# EEZ_XMOS_eval_r1B4.net
KiCad netlist of a schematic drawn in EAGLE
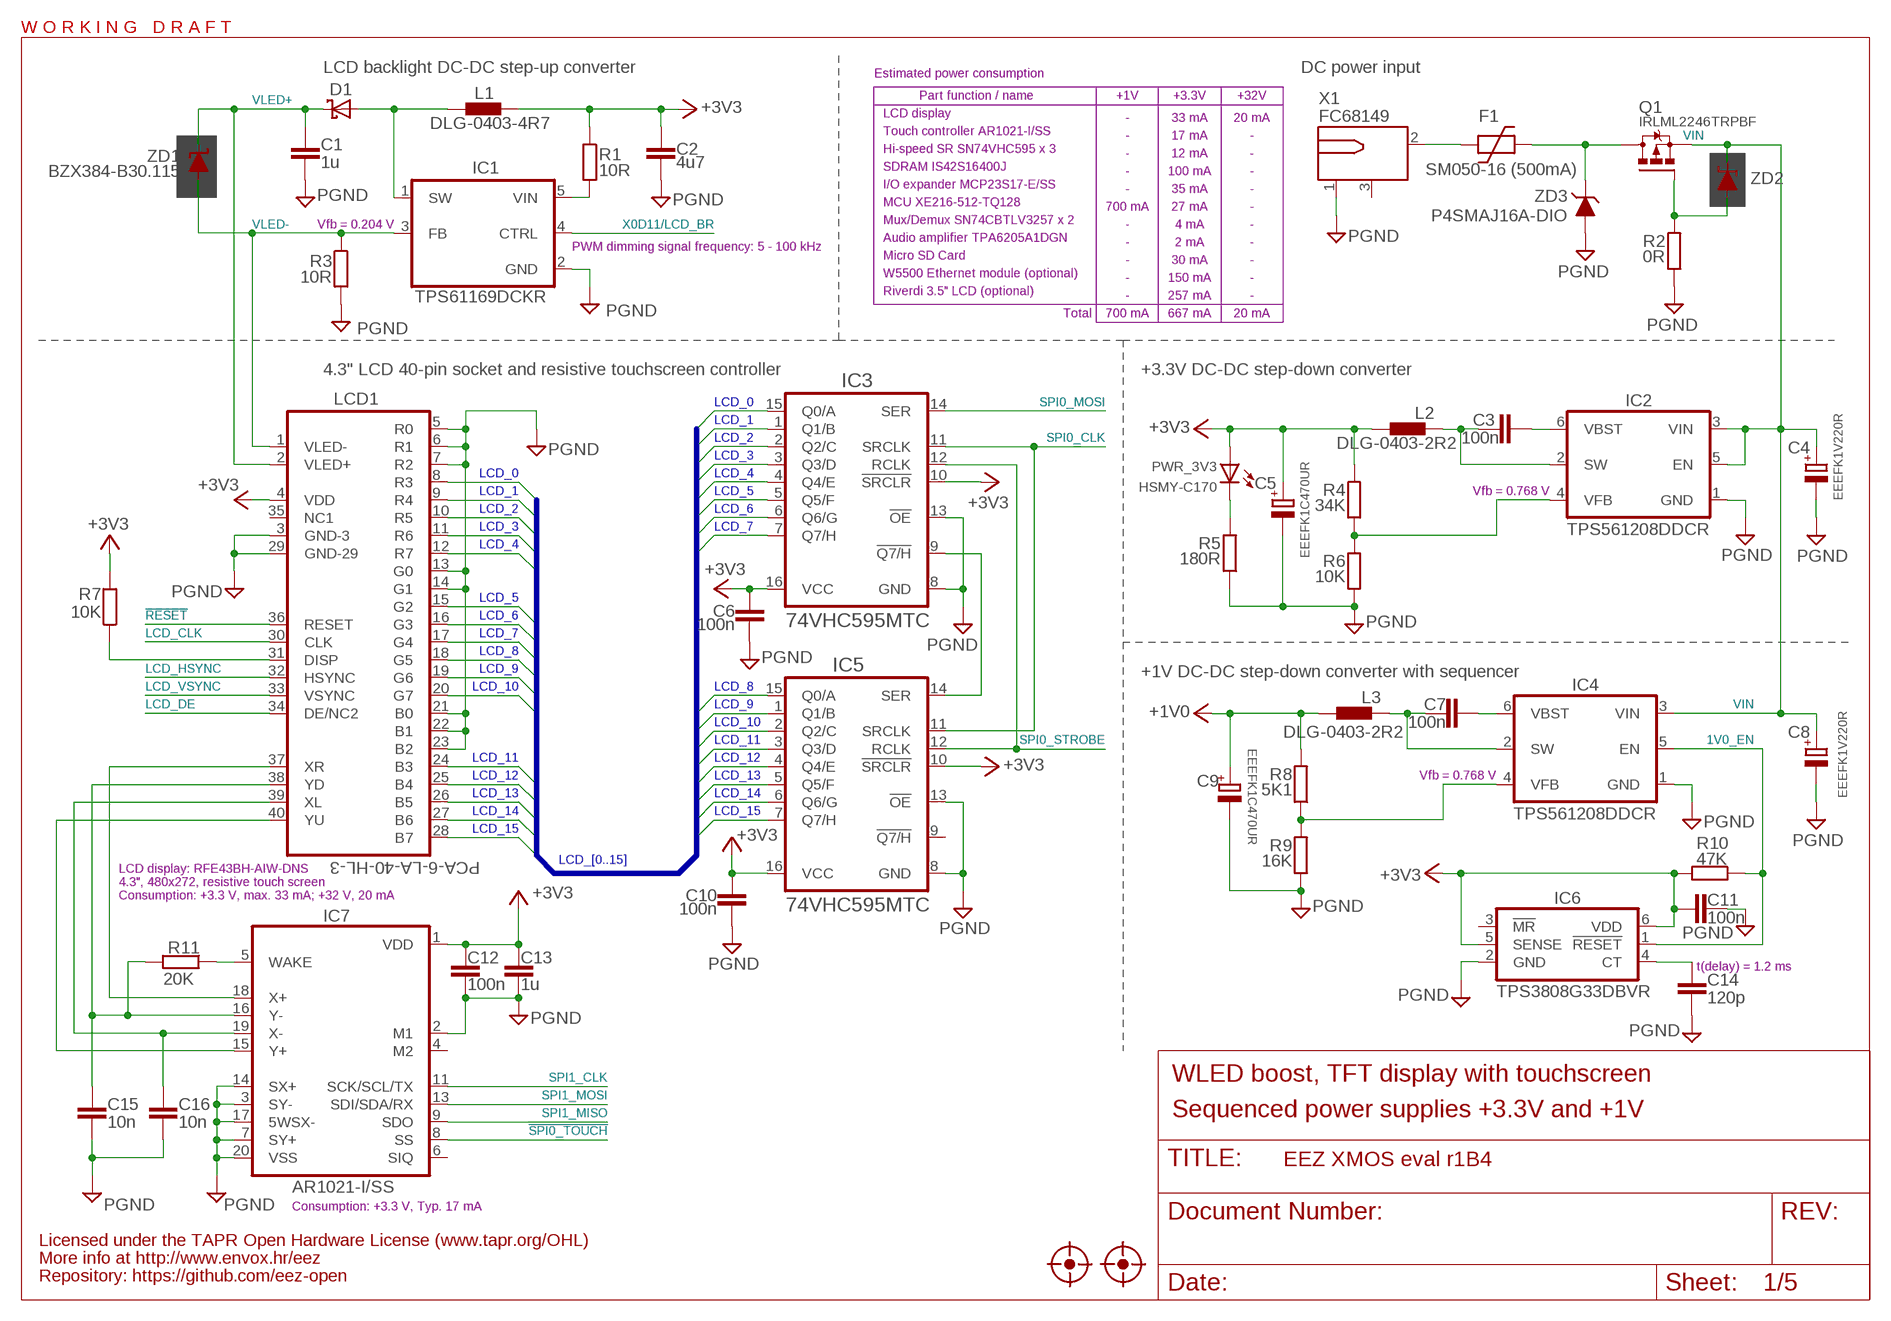
[diagram p0: schematic, sheet 1]
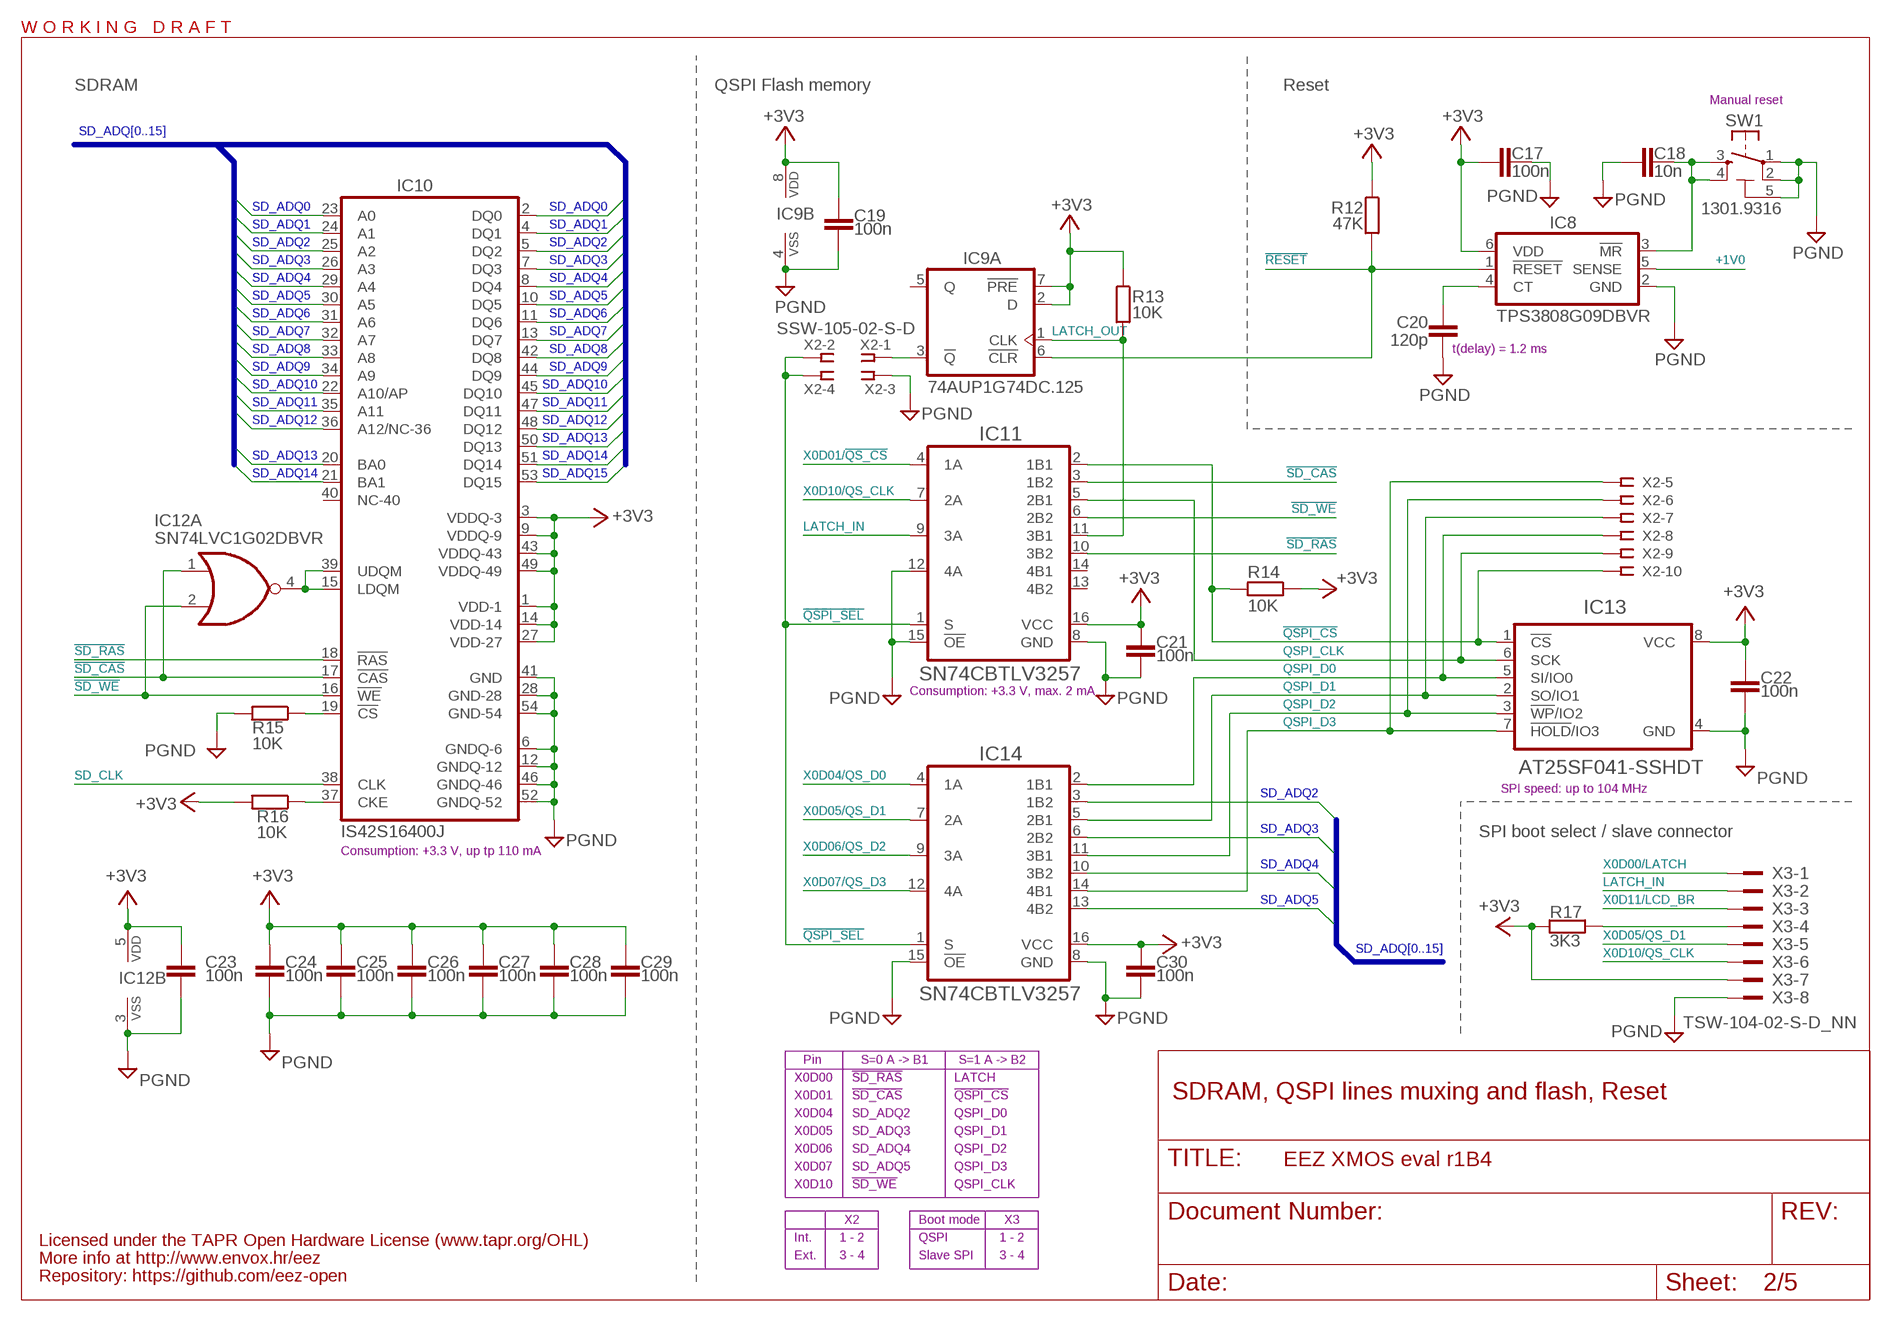
[diagram p1: schematic, sheet 2]
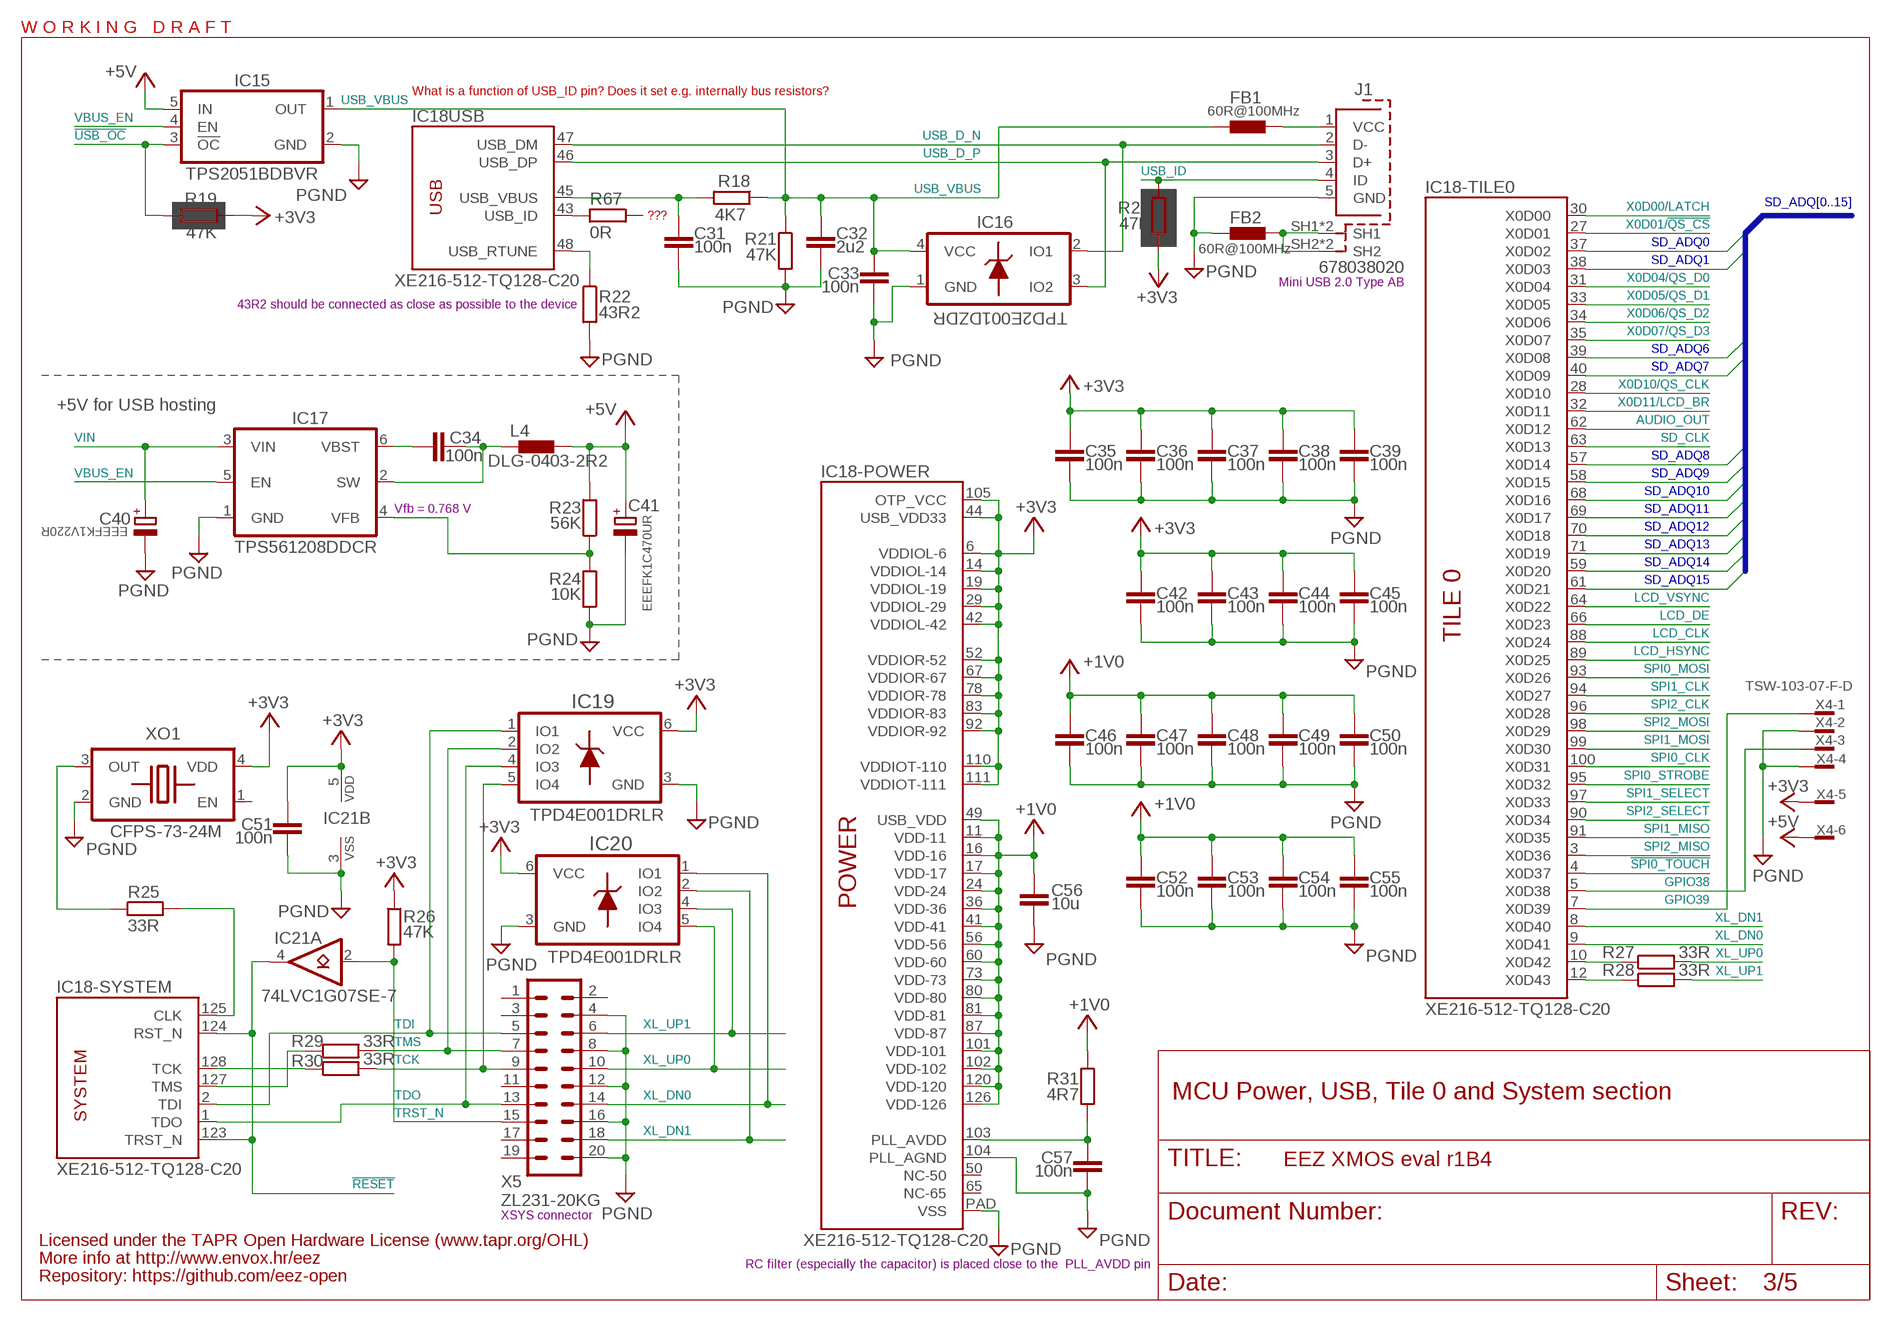
[diagram p2: schematic, sheet 3]
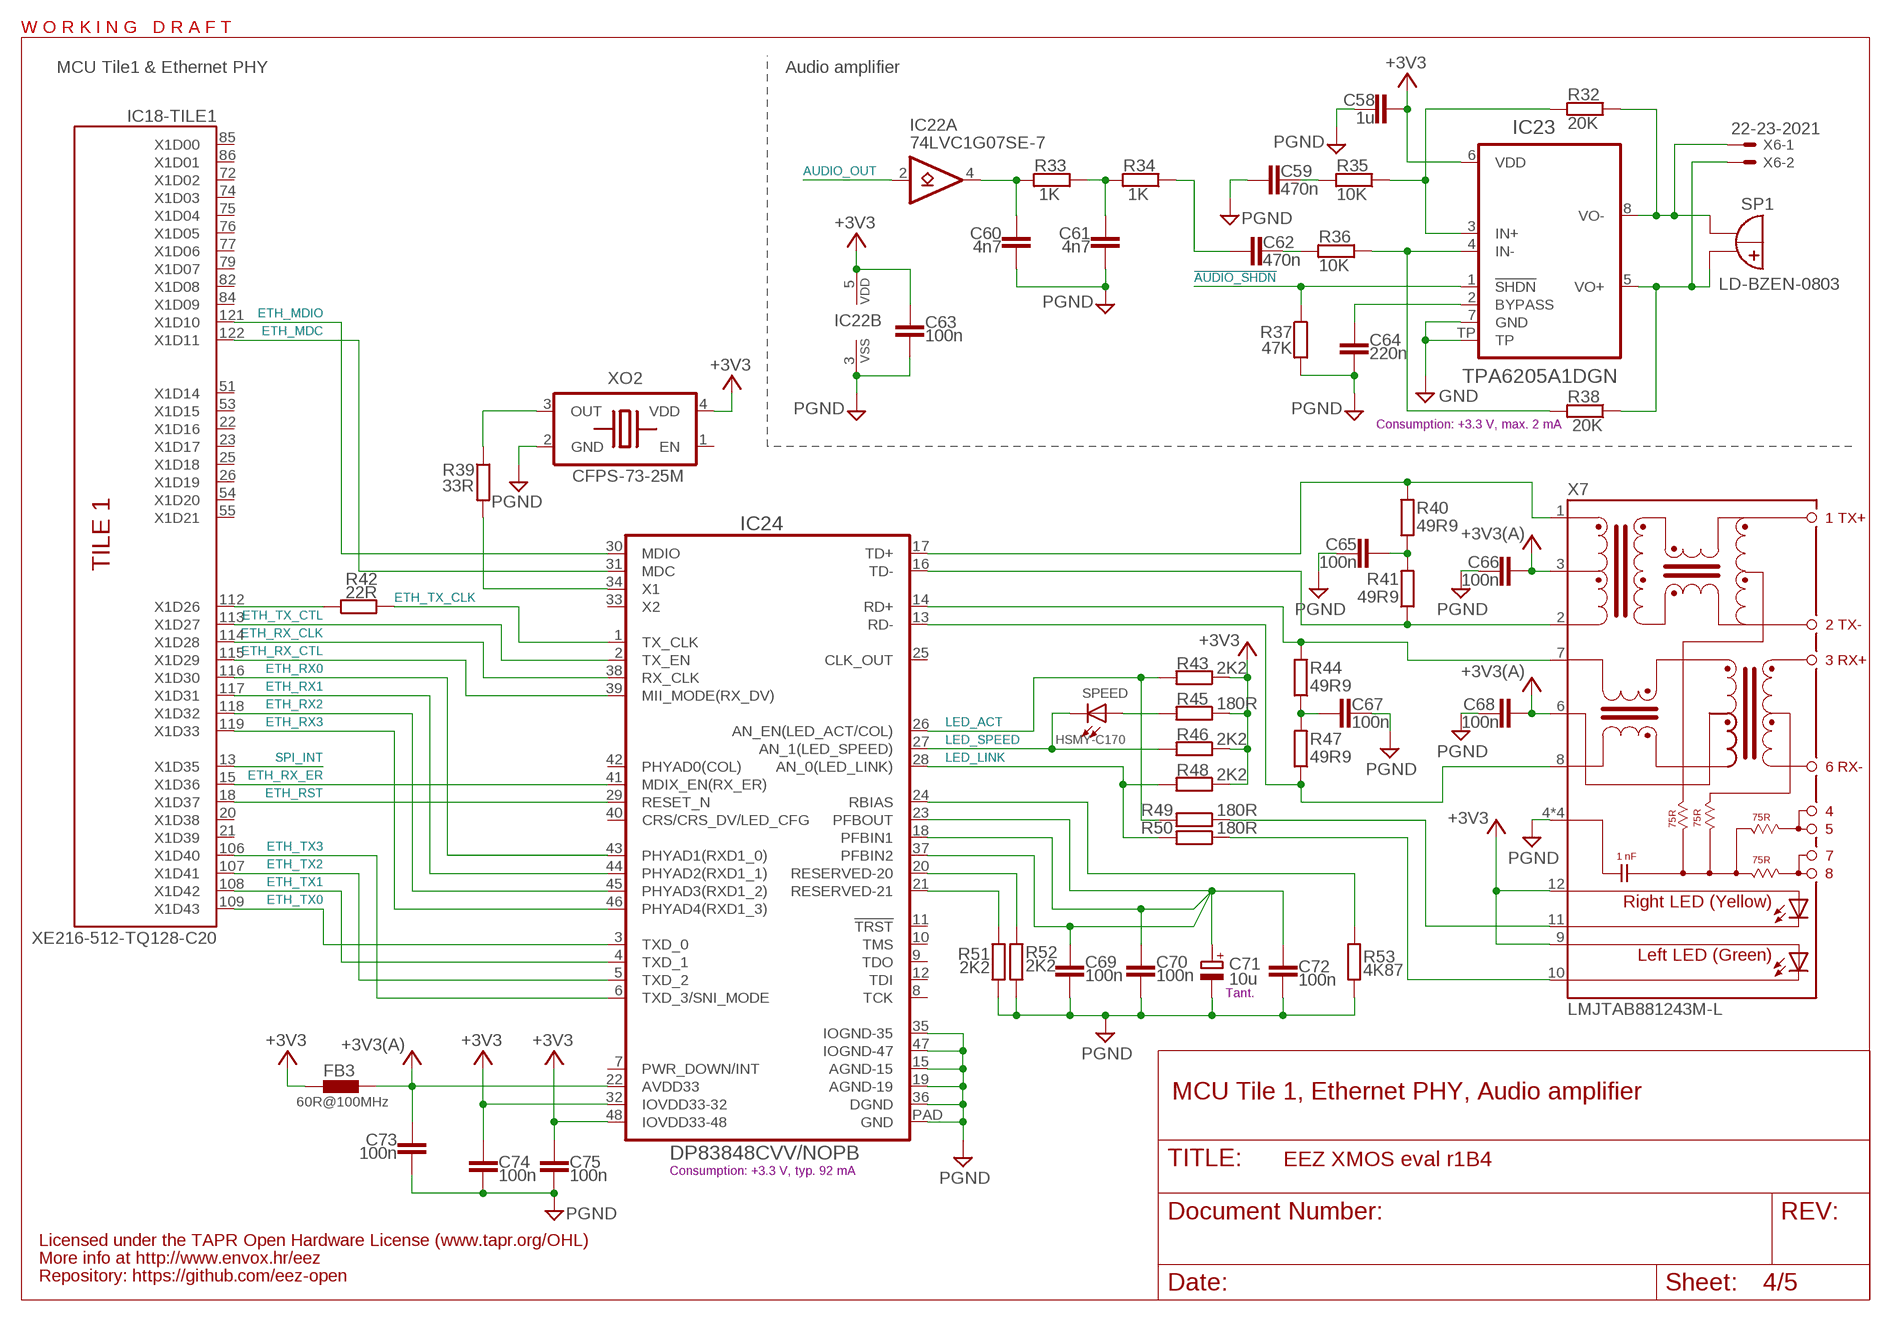
[diagram p3: schematic, sheet 4]
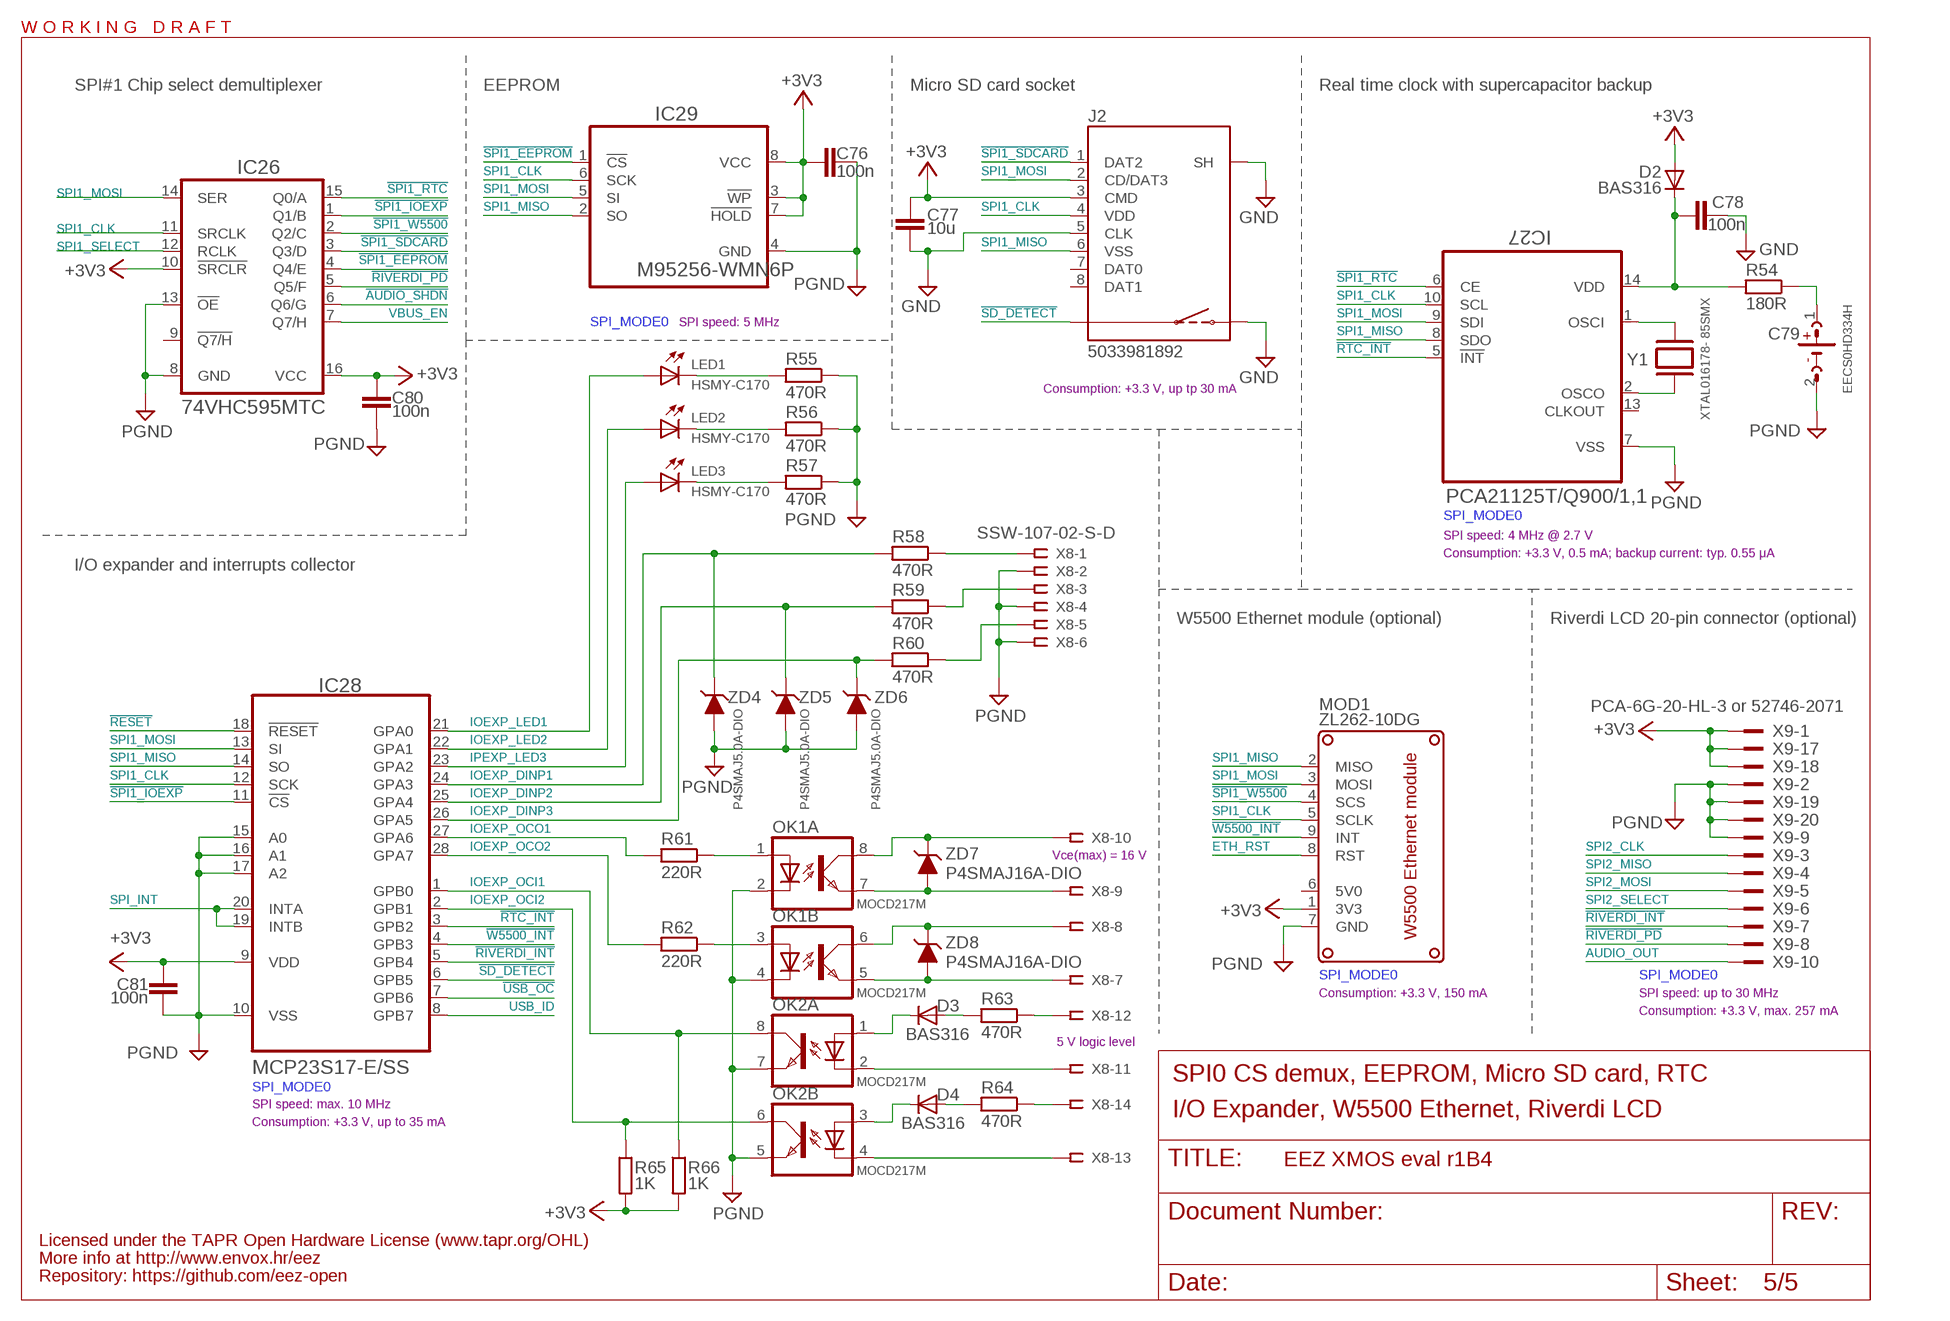
[diagram p4: schematic, sheet 5]

(export (version "E")
  (design (tool "Eeschema 10.0.6"))
  (components
    (comp (ref "C31")
      (value "100n")
      (footprint "eagle-import:C0603")
      (libsource (lib "eagle-import") (part "C-EUC0603"))
    )
    (comp (ref "C32")
      (value "2u2")
      (footprint "eagle-import:C0805")
      (libsource (lib "eagle-import") (part "C-EUC0805"))
    )
    (comp (ref "C33")
      (value "100n")
      (footprint "eagle-import:C0603")
      (libsource (lib "eagle-import") (part "C-EUC0603"))
    )
    (comp (ref "C34")
      (value "100n")
      (footprint "eagle-import:C0603")
      (libsource (lib "eagle-import") (part "C-EUC0603"))
    )
    (comp (ref "C35")
      (value "100n")
      (footprint "eagle-import:C0603")
      (libsource (lib "eagle-import") (part "C-EUC0603"))
    )
    (comp (ref "C36")
      (value "100n")
      (footprint "eagle-import:C0603")
      (libsource (lib "eagle-import") (part "C-EUC0603"))
    )
    (comp (ref "C37")
      (value "100n")
      (footprint "eagle-import:C0603")
      (libsource (lib "eagle-import") (part "C-EUC0603"))
    )
    (comp (ref "C38")
      (value "100n")
      (footprint "eagle-import:C0603")
      (libsource (lib "eagle-import") (part "C-EUC0603"))
    )
    (comp (ref "C39")
      (value "100n")
      (footprint "eagle-import:C0603")
      (libsource (lib "eagle-import") (part "C-EUC0603"))
    )
    (comp (ref "C40")
      (value "EEEFK1V220R")
      (footprint "eagle-import:CAPAE530X610N")
      (fields (field (name "MPN") "EEE-FK1V100R") (field (name "TOLERANCE") "±20 %"))
      (libsource (lib "eagle-import") (part "EEE--CASE-CFK1V100R"))
    )
    (comp (ref "C41")
      (value "EEEFK1C470UR")
      (footprint "eagle-import:CAPAE530X610N")
      (fields
        (field (name "MPN") "EEE-FK1V100R")
        (field (name "TOLERANCE") "±20 %")
        (field (name "MPN_1") "EEE-FK1V100R")
        (field (name "OC_FARNELL") "1850112  ")
        (field (name "OC_NEWARK") "23T0867")
        (field (name "PACKAGE") "CASE-C")
        (field (name "SUPPLIER") "PANASONIC")
        (field (name "TOLERANCE_1") "±20 %")
        (field (name "VOLTAGERATING") "35V")
      )
      (libsource (lib "eagle-import") (part "EEE--CASE-CFK1V100R"))
    )
    (comp (ref "C42")
      (value "100n")
      (footprint "eagle-import:C0603")
      (libsource (lib "eagle-import") (part "C-EUC0603"))
    )
    (comp (ref "C43")
      (value "100n")
      (footprint "eagle-import:C0603")
      (libsource (lib "eagle-import") (part "C-EUC0603"))
    )
    (comp (ref "C44")
      (value "100n")
      (footprint "eagle-import:C0603")
      (libsource (lib "eagle-import") (part "C-EUC0603"))
    )
    (comp (ref "C45")
      (value "100n")
      (footprint "eagle-import:C0603")
      (libsource (lib "eagle-import") (part "C-EUC0603"))
    )
    (comp (ref "C46")
      (value "100n")
      (footprint "eagle-import:C0603")
      (libsource (lib "eagle-import") (part "C-EUC0603"))
    )
    (comp (ref "C47")
      (value "100n")
      (footprint "eagle-import:C0603")
      (libsource (lib "eagle-import") (part "C-EUC0603"))
    )
    (comp (ref "C48")
      (value "100n")
      (footprint "eagle-import:C0603")
      (libsource (lib "eagle-import") (part "C-EUC0603"))
    )
    (comp (ref "C49")
      (value "100n")
      (footprint "eagle-import:C0603")
      (libsource (lib "eagle-import") (part "C-EUC0603"))
    )
    (comp (ref "C50")
      (value "100n")
      (footprint "eagle-import:C0603")
      (libsource (lib "eagle-import") (part "C-EUC0603"))
    )
    (comp (ref "C51")
      (value "100n")
      (footprint "eagle-import:C0603")
      (libsource (lib "eagle-import") (part "C-EUC0603"))
    )
    (comp (ref "C52")
      (value "100n")
      (footprint "eagle-import:C0603")
      (libsource (lib "eagle-import") (part "C-EUC0603"))
    )
    (comp (ref "C53")
      (value "100n")
      (footprint "eagle-import:C0603")
      (libsource (lib "eagle-import") (part "C-EUC0603"))
    )
    (comp (ref "C54")
      (value "100n")
      (footprint "eagle-import:C0603")
      (libsource (lib "eagle-import") (part "C-EUC0603"))
    )
    (comp (ref "C55")
      (value "100n")
      (footprint "eagle-import:C0603")
      (libsource (lib "eagle-import") (part "C-EUC0603"))
    )
    (comp (ref "C56")
      (value "10u")
      (footprint "eagle-import:C1210")
      (libsource (lib "eagle-import") (part "C-EUC1210"))
    )
    (comp (ref "C57")
      (value "100n")
      (footprint "eagle-import:C0603")
      (libsource (lib "eagle-import") (part "C-EUC0603"))
    )
    (comp (ref "FB1")
      (value "60R@100MHz")
      (footprint "eagle-import:BEAD0603")
      (libsource (lib "eagle-import") (part "FERRITE_BEAD0603"))
    )
    (comp (ref "FB2")
      (value "60R@100MHz")
      (footprint "eagle-import:BEAD0603")
      (libsource (lib "eagle-import") (part "FERRITE_BEAD0603"))
    )
    (comp (ref "IC15")
      (value "TPS2051BDBVR")
      (footprint "eagle-import:DBV5")
      (libsource (lib "eagle-import") (part "TPS2051B"))
    )
    (comp (ref "IC16")
      (value "TPD2E001DZDR")
      (footprint "eagle-import:SOP192P292X122-4N")
      (libsource (lib "eagle-import") (part "TPD2E001DZDR"))
    )
    (comp (ref "IC17")
      (value "TPS561208DDCR")
      (footprint "eagle-import:DBV6")
      (libsource (lib "eagle-import") (part "TPS56120X"))
    )
    (comp (ref "IC18")
      (value "XE216-512-TQ128-C20")
      (footprint "eagle-import:TQ128")
      (libsource (lib "eagle-import") (part "XE216-TQ128"))
    )
    (comp (ref "IC19")
      (value "TPD4E001DRLR")
      (footprint "eagle-import:DRL6")
      (libsource (lib "eagle-import") (part "TPD4E001-DRL"))
    )
    (comp (ref "IC20")
      (value "TPD4E001DRLR")
      (footprint "eagle-import:DRL6")
      (libsource (lib "eagle-import") (part "TPD4E001-DRL"))
    )
    (comp (ref "IC21")
      (value "74LVC1G07SE-7")
      (footprint "eagle-import:DCK5")
      (libsource (lib "eagle-import") (part "SN74LVC1G07-SC70"))
    )
    (comp (ref "J1")
      (value "678038020")
      (footprint "eagle-import:678038020")
      (libsource (lib "eagle-import") (part "678038020"))
    )
    (comp (ref "L4")
      (value "DLG-0403-2R2")
      (footprint "eagle-import:DE0403")
      (libsource (lib "eagle-import") (part "DE0403"))
    )
    (comp (ref "R18")
      (value "4K7")
      (footprint "eagle-import:R0805")
      (libsource (lib "eagle-import") (part "R-EU_R0805"))
    )
    (comp (ref "R19")
      (value "47K")
      (footprint "eagle-import:R0805")
      (libsource (lib "eagle-import") (part "R-EU_R0805"))
    )
    (comp (ref "R20")
      (value "47K")
      (footprint "eagle-import:R0805")
      (libsource (lib "eagle-import") (part "R-EU_R0805"))
    )
    (comp (ref "R21")
      (value "47K")
      (footprint "eagle-import:R0805")
      (libsource (lib "eagle-import") (part "R-EU_R0805"))
    )
    (comp (ref "R22")
      (value "43R2")
      (footprint "eagle-import:R0805")
      (libsource (lib "eagle-import") (part "R-EU_R0805"))
    )
    (comp (ref "R23")
      (value "56K")
      (footprint "eagle-import:R0805")
      (libsource (lib "eagle-import") (part "R-EU_R0805"))
    )
    (comp (ref "R24")
      (value "10K")
      (footprint "eagle-import:R0805")
      (libsource (lib "eagle-import") (part "R-EU_R0805"))
    )
    (comp (ref "R25")
      (value "33R")
      (footprint "eagle-import:R0603")
      (libsource (lib "eagle-import") (part "R-EU_R0603"))
    )
    (comp (ref "R26")
      (value "47K")
      (footprint "eagle-import:R0805")
      (libsource (lib "eagle-import") (part "R-EU_R0805"))
    )
    (comp (ref "R27")
      (value "33R")
      (footprint "eagle-import:R0603")
      (libsource (lib "eagle-import") (part "R-EU_R0603"))
    )
    (comp (ref "R28")
      (value "33R")
      (footprint "eagle-import:R0603")
      (libsource (lib "eagle-import") (part "R-EU_R0603"))
    )
    (comp (ref "R29")
      (value "33R")
      (footprint "eagle-import:R0603")
      (libsource (lib "eagle-import") (part "R-EU_R0603"))
    )
    (comp (ref "R30")
      (value "33R")
      (footprint "eagle-import:R0603")
      (libsource (lib "eagle-import") (part "R-EU_R0603"))
    )
    (comp (ref "R31")
      (value "4R7")
      (footprint "eagle-import:R0805")
      (libsource (lib "eagle-import") (part "R-EU_R0805"))
    )
    (comp (ref "R67")
      (value "0R")
      (footprint "eagle-import:R0805")
      (libsource (lib "eagle-import") (part "R-EU_R0805"))
    )
    (comp (ref "X4")
      (value "TSW-103-07-F-D")
      (footprint "eagle-import:TSW-103-07-F-D")
      (libsource (lib "eagle-import") (part "TSW-103-07-F-D"))
    )
    (comp (ref "X5")
      (value "ZL231-20KG")
      (footprint "eagle-import:ML20L")
      (libsource (lib "eagle-import") (part "ML20L"))
    )
    (comp (ref "XO1")
      (value "CFPS-73-24M")
      (footprint "eagle-import:12SMX(C)")
      (libsource (lib "eagle-import") (part "XO-7X5MM"))
    )
    (comp (ref "C76")
      (value "100n")
      (footprint "eagle-import:C0603")
      (libsource (lib "eagle-import") (part "C-EUC0603"))
    )
    (comp (ref "C77")
      (value "10u")
      (footprint "eagle-import:C1210")
      (libsource (lib "eagle-import") (part "C-EUC1210"))
    )
    (comp (ref "C78")
      (value "100n")
      (footprint "eagle-import:C0603")
      (libsource (lib "eagle-import") (part "C-EUC0603"))
    )
    (comp (ref "C79")
      (value "EECS0HD334H")
      (footprint "eagle-import:SG-R10MM")
      (libsource (lib "eagle-import") (part "SUPER_CAP-10"))
    )
    (comp (ref "C80")
      (value "100n")
      (footprint "eagle-import:C0603")
      (libsource (lib "eagle-import") (part "C-EUC0603"))
    )
    (comp (ref "C81")
      (value "100n")
      (footprint "eagle-import:C0603")
      (libsource (lib "eagle-import") (part "C-EUC0603"))
    )
    (comp (ref "D2")
      (value "BAS316")
      (footprint "eagle-import:SOD323-W")
      (libsource (lib "eagle-import") (part "DIODE-SOD323-W"))
    )
    (comp (ref "D3")
      (value "BAS316")
      (footprint "eagle-import:SOD323-W")
      (libsource (lib "eagle-import") (part "DIODE-SOD323-W"))
    )
    (comp (ref "D4")
      (value "BAS316")
      (footprint "eagle-import:SOD323-W")
      (libsource (lib "eagle-import") (part "DIODE-SOD323-W"))
    )
    (comp (ref "IC26")
      (value "74VHC595MTC")
      (footprint "eagle-import:PW(R-PDSO-G16)")
      (libsource (lib "eagle-import") (part "SN74HC595TSSOP"))
    )
    (comp (ref "IC27")
      (value "PCA21125T/Q900/1,1")
      (footprint "eagle-import:SOP65P640X120-14N")
      (libsource (lib "eagle-import") (part "PCA21125TSSOP-14"))
    )
    (comp (ref "IC28")
      (value "MCP23S17-E/SS")
      (footprint "eagle-import:SOP65P780X200-28N")
      (libsource (lib "eagle-import") (part "MCP23S17-E/SS"))
    )
    (comp (ref "IC29")
      (value "M95256-WMN6P")
      (footprint "eagle-import:SOIC127P600X175-8N")
      (libsource (lib "eagle-import") (part "AT25XXXSOIC8"))
    )
    (comp (ref "J2")
      (value "5033981892")
      (footprint "eagle-import:5033981892")
      (libsource (lib "eagle-import") (part "5033981892"))
    )
    (comp (ref "LED1")
      (value "HSMY-C170")
      (footprint "eagle-import:LED_0805")
      (libsource (lib "eagle-import") (part "LED0805"))
    )
    (comp (ref "LED2")
      (value "HSMY-C170")
      (footprint "eagle-import:LED_0805")
      (libsource (lib "eagle-import") (part "LED0805"))
    )
    (comp (ref "LED3")
      (value "HSMY-C170")
      (footprint "eagle-import:LED_0805")
      (libsource (lib "eagle-import") (part "LED0805"))
    )
    (comp (ref "MOD1")
      (value "ZL262-10DG")
      (footprint "eagle-import:ETH_W5500_MODULE")
      (libsource (lib "eagle-import") (part "ETH_W5500_MODULE"))
    )
    (comp (ref "OK1")
      (value "MOCD217M")
      (footprint "eagle-import:SO8-OPTO")
      (libsource (lib "eagle-import") (part "MOCD217"))
    )
    (comp (ref "OK2")
      (value "MOCD217M")
      (footprint "eagle-import:SO8-OPTO")
      (libsource (lib "eagle-import") (part "MOCD217"))
    )
    (comp (ref "R54")
      (value "180R")
      (footprint "eagle-import:R0805")
      (libsource (lib "eagle-import") (part "R-EU_R0805"))
    )
    (comp (ref "R55")
      (value "470R")
      (footprint "eagle-import:R0805")
      (libsource (lib "eagle-import") (part "R-EU_R0805"))
    )
    (comp (ref "R56")
      (value "470R")
      (footprint "eagle-import:R0805")
      (libsource (lib "eagle-import") (part "R-EU_R0805"))
    )
    (comp (ref "R57")
      (value "470R")
      (footprint "eagle-import:R0805")
      (libsource (lib "eagle-import") (part "R-EU_R0805"))
    )
    (comp (ref "R58")
      (value "470R")
      (footprint "eagle-import:R0805")
      (libsource (lib "eagle-import") (part "R-EU_R0805"))
    )
    (comp (ref "R59")
      (value "470R")
      (footprint "eagle-import:R0805")
      (libsource (lib "eagle-import") (part "R-EU_R0805"))
    )
    (comp (ref "R60")
      (value "470R")
      (footprint "eagle-import:R0805")
      (libsource (lib "eagle-import") (part "R-EU_R0805"))
    )
    (comp (ref "R61")
      (value "220R")
      (footprint "eagle-import:R0805")
      (libsource (lib "eagle-import") (part "R-EU_R0805"))
    )
    (comp (ref "R62")
      (value "220R")
      (footprint "eagle-import:R0805")
      (libsource (lib "eagle-import") (part "R-EU_R0805"))
    )
    (comp (ref "R63")
      (value "470R")
      (footprint "eagle-import:R0805")
      (libsource (lib "eagle-import") (part "R-EU_R0805"))
    )
    (comp (ref "R64")
      (value "470R")
      (footprint "eagle-import:R0805")
      (libsource (lib "eagle-import") (part "R-EU_R0805"))
    )
    (comp (ref "R65")
      (value "1K")
      (footprint "eagle-import:R0805")
      (libsource (lib "eagle-import") (part "R-EU_R0805"))
    )
    (comp (ref "R66")
      (value "1K")
      (footprint "eagle-import:R0805")
      (libsource (lib "eagle-import") (part "R-EU_R0805"))
    )
    (comp (ref "X8")
      (value "SSW-107-02-S-D")
      (footprint "eagle-import:SSW-107-02-S-D")
      (libsource (lib "eagle-import") (part "SSW-107-02-S-D"))
    )
    (comp (ref "X9")
      (value "PCA-6G-20-HL-3 or 52746-2071")
      (footprint "eagle-import:FPC-20_ROTATED")
      (libsource (lib "eagle-import") (part "WR-FPC_68712014522_ROTATED"))
    )
    (comp (ref "Y1")
      (value "XTAL016178- 85SMX")
      (footprint "eagle-import:85SMX")
      (libsource (lib "eagle-import") (part "XTAL85SMX"))
    )
    (comp (ref "ZD4")
      (value "P4SMAJ5.0A-DIO")
      (footprint "eagle-import:DO214AC")
      (libsource (lib "eagle-import") (part "PSMAXX"))
    )
    (comp (ref "ZD5")
      (value "P4SMAJ5.0A-DIO")
      (footprint "eagle-import:DO214AC")
      (libsource (lib "eagle-import") (part "PSMAXX"))
    )
    (comp (ref "ZD6")
      (value "P4SMAJ5.0A-DIO")
      (footprint "eagle-import:DO214AC")
      (libsource (lib "eagle-import") (part "PSMAXX"))
    )
    (comp (ref "ZD7")
      (value "P4SMAJ16A-DIO")
      (footprint "eagle-import:DO214AC")
      (libsource (lib "eagle-import") (part "PSMAXX"))
    )
    (comp (ref "ZD8")
      (value "P4SMAJ16A-DIO")
      (footprint "eagle-import:DO214AC")
      (libsource (lib "eagle-import") (part "PSMAXX"))
    )
    (comp (ref "C1")
      (value "1u")
      (footprint "eagle-import:C0805")
      (libsource (lib "eagle-import") (part "C-EUC0805"))
    )
    (comp (ref "C2")
      (value "4u7")
      (footprint "eagle-import:C1206")
      (libsource (lib "eagle-import") (part "C-EUC1206"))
    )
    (comp (ref "C3")
      (value "100n")
      (footprint "eagle-import:C0603")
      (libsource (lib "eagle-import") (part "C-EUC0603"))
    )
    (comp (ref "C4")
      (value "EEEFK1V220R")
      (footprint "eagle-import:CAPAE530X610N")
      (fields (field (name "MPN") "EEE-FK1V100R") (field (name "TOLERANCE") "±20 %"))
      (libsource (lib "eagle-import") (part "EEE--CASE-CFK1V100R"))
    )
    (comp (ref "C5")
      (value "EEEFK1C470UR")
      (footprint "eagle-import:CAPAE530X610N")
      (fields
        (field (name "MPN") "EEE-FK1V100R")
        (field (name "TOLERANCE") "±20 %")
        (field (name "MPN_1") "EEE-FK1V100R")
        (field (name "OC_FARNELL") "1850112  ")
        (field (name "OC_NEWARK") "23T0867")
        (field (name "PACKAGE") "CASE-C")
        (field (name "SUPPLIER") "PANASONIC")
        (field (name "TOLERANCE_1") "±20 %")
        (field (name "VOLTAGERATING") "35V")
      )
      (libsource (lib "eagle-import") (part "EEE--CASE-CFK1V100R"))
    )
    (comp (ref "C6")
      (value "100n")
      (footprint "eagle-import:C0603")
      (libsource (lib "eagle-import") (part "C-EUC0603"))
    )
    (comp (ref "C7")
      (value "100n")
      (footprint "eagle-import:C0603")
      (libsource (lib "eagle-import") (part "C-EUC0603"))
    )
    (comp (ref "C8")
      (value "EEEFK1V220R")
      (footprint "eagle-import:CAPAE530X610N")
      (fields
        (field (name "MPN") "EEE-FK1V100R")
        (field (name "TOLERANCE") "±20 %")
        (field (name "MPN_1") "EEE-FK1V100R")
        (field (name "OC_FARNELL") "1850112  ")
        (field (name "OC_NEWARK") "23T0867")
        (field (name "PACKAGE") "CASE-C")
        (field (name "SUPPLIER") "PANASONIC")
        (field (name "TOLERANCE_1") "±20 %")
        (field (name "VOLTAGERATING") "35V")
      )
      (libsource (lib "eagle-import") (part "EEE--CASE-CFK1V100R"))
    )
    (comp (ref "C9")
      (value "EEEFK1C470UR")
      (footprint "eagle-import:CAPAE530X610N")
      (fields
        (field (name "MPN") "EEE-FK1V100R")
        (field (name "TOLERANCE") "±20 %")
        (field (name "MPN_1") "EEE-FK1V100R")
        (field (name "OC_FARNELL") "1850112  ")
        (field (name "OC_NEWARK") "23T0867")
        (field (name "PACKAGE") "CASE-C")
        (field (name "SUPPLIER") "PANASONIC")
        (field (name "TOLERANCE_1") "±20 %")
        (field (name "VOLTAGERATING") "35V")
      )
      (libsource (lib "eagle-import") (part "EEE--CASE-CFK1V100R"))
    )
    (comp (ref "C10")
      (value "100n")
      (footprint "eagle-import:C0603")
      (libsource (lib "eagle-import") (part "C-EUC0603"))
    )
    (comp (ref "C11")
      (value "100n")
      (footprint "eagle-import:C0603")
      (libsource (lib "eagle-import") (part "C-EUC0603"))
    )
    (comp (ref "C12")
      (value "100n")
      (footprint "eagle-import:C0603")
      (libsource (lib "eagle-import") (part "C-EUC0603"))
    )
    (comp (ref "C13")
      (value "1u")
      (footprint "eagle-import:C0805")
      (libsource (lib "eagle-import") (part "C-EUC0805"))
    )
    (comp (ref "C14")
      (value "120p")
      (footprint "eagle-import:C0805")
      (libsource (lib "eagle-import") (part "C-EUC0805"))
    )
    (comp (ref "C15")
      (value "10n")
      (footprint "eagle-import:C0805")
      (libsource (lib "eagle-import") (part "C-EUC0805"))
    )
    (comp (ref "C16")
      (value "10n")
      (footprint "eagle-import:C0805")
      (libsource (lib "eagle-import") (part "C-EUC0805"))
    )
    (comp (ref "D1")
      (value "SCHOTTKYSOD123")
      (footprint "eagle-import:SOD123")
      (libsource (lib "eagle-import") (part "SCHOTTKYSOD123"))
    )
    (comp (ref "F1")
      (value "SM050-16 (500mA)")
      (footprint "eagle-import:F1210")
      (libsource (lib "eagle-import") (part "FUSE_RESETTABLE21210"))
    )
    (comp (ref "FM1")
      (value "FIDUCIAL_2")
      (footprint "eagle-import:FIDUCIAL_DUAL")
      (libsource (lib "eagle-import") (part "FIDUCIAL_2"))
    )
    (comp (ref "FM2")
      (value "FIDUCIAL_2")
      (footprint "eagle-import:FIDUCIAL_DUAL")
      (libsource (lib "eagle-import") (part "FIDUCIAL_2"))
    )
    (comp (ref "IC1")
      (value "TPS61169DCKR")
      (footprint "eagle-import:DCK0005A_N")
      (fields (field (name "MANUFACTURER") "Texas Instruments"))
      (libsource (lib "eagle-import") (part "TPS61169DCKR"))
    )
    (comp (ref "IC2")
      (value "TPS561208DDCR")
      (footprint "eagle-import:DBV6")
      (libsource (lib "eagle-import") (part "TPS56120X"))
    )
    (comp (ref "IC3")
      (value "74VHC595MTC")
      (footprint "eagle-import:PW(R-PDSO-G16)")
      (libsource (lib "eagle-import") (part "SN74HC595TSSOP"))
    )
    (comp (ref "IC4")
      (value "TPS561208DDCR")
      (footprint "eagle-import:DBV6")
      (libsource (lib "eagle-import") (part "TPS56120X"))
    )
    (comp (ref "IC5")
      (value "74VHC595MTC")
      (footprint "eagle-import:PW(R-PDSO-G16)")
      (libsource (lib "eagle-import") (part "SN74HC595TSSOP"))
    )
    (comp (ref "IC6")
      (value "TPS3808G33DBVR")
      (footprint "eagle-import:DBV6")
      (fields
        (field (name "GENERIC_PART_NUMBER") "TPS3808G01")
        (field (name "MANUFACTURER") "Texas Instruments")
        (field (name "MANUFACTURER_PART_NUMBER") "tps3808g01_dbv_6")
      )
      (libsource (lib "eagle-import") (part "TPS3808"))
    )
    (comp (ref "IC7")
      (value "AR1021-I/SS")
      (footprint "eagle-import:SOP65P780X200-20N")
      (libsource (lib "eagle-import") (part "AR1021-I/SS"))
    )
    (comp (ref "L1")
      (value "DLG-0403-4R7")
      (footprint "eagle-import:DE0403")
      (libsource (lib "eagle-import") (part "DE0403"))
    )
    (comp (ref "L2")
      (value "DLG-0403-2R2")
      (footprint "eagle-import:DE0403")
      (libsource (lib "eagle-import") (part "DE0403"))
    )
    (comp (ref "L3")
      (value "DLG-0403-2R2")
      (footprint "eagle-import:DE0403")
      (libsource (lib "eagle-import") (part "DE0403"))
    )
    (comp (ref "LCD1")
      (value "PCA-6-LA-40-HL-3")
      (footprint "eagle-import:FPC_40")
      (libsource (lib "eagle-import") (part "RFE430Y-AIW-DNS"))
    )
    (comp (ref "PWR_3V3")
      (value "HSMY-C170")
      (footprint "eagle-import:LED_0805")
      (libsource (lib "eagle-import") (part "LED0805"))
    )
    (comp (ref "Q1")
      (value "IRLML2246TRPBF")
      (footprint "eagle-import:SOT95P237X112-3N")
      (libsource (lib "eagle-import") (part "IRLML2246TRPBF"))
    )
    (comp (ref "R1")
      (value "10R")
      (footprint "eagle-import:R1206")
      (libsource (lib "eagle-import") (part "R-EU_R1206"))
    )
    (comp (ref "R2")
      (value "0R")
      (footprint "eagle-import:R0805")
      (libsource (lib "eagle-import") (part "R-EU_R0805"))
    )
    (comp (ref "R3")
      (value "10R")
      (footprint "eagle-import:R1206")
      (libsource (lib "eagle-import") (part "R-EU_R1206"))
    )
    (comp (ref "R4")
      (value "34K")
      (footprint "eagle-import:R0805")
      (libsource (lib "eagle-import") (part "R-EU_R0805"))
    )
    (comp (ref "R5")
      (value "180R")
      (footprint "eagle-import:R0805")
      (libsource (lib "eagle-import") (part "R-EU_R0805"))
    )
    (comp (ref "R6")
      (value "10K")
      (footprint "eagle-import:R0805")
      (libsource (lib "eagle-import") (part "R-EU_R0805"))
    )
    (comp (ref "R7")
      (value "10K")
      (footprint "eagle-import:R0805")
      (libsource (lib "eagle-import") (part "R-EU_R0805"))
    )
    (comp (ref "R8")
      (value "5K1")
      (footprint "eagle-import:R0805")
      (libsource (lib "eagle-import") (part "R-EU_R0805"))
    )
    (comp (ref "R9")
      (value "16K")
      (footprint "eagle-import:R0805")
      (libsource (lib "eagle-import") (part "R-EU_R0805"))
    )
    (comp (ref "R10")
      (value "47K")
      (footprint "eagle-import:R0805")
      (libsource (lib "eagle-import") (part "R-EU_R0805"))
    )
    (comp (ref "R11")
      (value "20K")
      (footprint "eagle-import:R0805")
      (libsource (lib "eagle-import") (part "R-EU_R0805"))
    )
    (comp (ref "X1")
      (value "FC68149")
      (footprint "eagle-import:DC-21MM")
      (libsource (lib "eagle-import") (part "DC21_PWRX"))
    )
    (comp (ref "ZD1")
      (value "BZX384-B30.115")
      (footprint "eagle-import:SOD323-W")
      (libsource (lib "eagle-import") (part "ZENER-DIODESOD323"))
    )
    (comp (ref "ZD2")
      (value "ZENER-DIODESOD323")
      (footprint "eagle-import:SOD323-W")
      (libsource (lib "eagle-import") (part "ZENER-DIODESOD323"))
    )
    (comp (ref "ZD3")
      (value "P4SMAJ16A-DIO")
      (footprint "eagle-import:DO214AC")
      (libsource (lib "eagle-import") (part "PSMAXX"))
    )
    (comp (ref "C17")
      (value "100n")
      (footprint "eagle-import:C0603")
      (libsource (lib "eagle-import") (part "C-EUC0603"))
    )
    (comp (ref "C18")
      (value "10n")
      (footprint "eagle-import:C0805")
      (libsource (lib "eagle-import") (part "C-EUC0805"))
    )
    (comp (ref "C19")
      (value "100n")
      (footprint "eagle-import:C0603")
      (libsource (lib "eagle-import") (part "C-EUC0603"))
    )
    (comp (ref "C20")
      (value "120p")
      (footprint "eagle-import:C0805")
      (libsource (lib "eagle-import") (part "C-EUC0805"))
    )
    (comp (ref "C21")
      (value "100n")
      (footprint "eagle-import:C0603")
      (libsource (lib "eagle-import") (part "C-EUC0603"))
    )
    (comp (ref "C22")
      (value "100n")
      (footprint "eagle-import:C0603")
      (libsource (lib "eagle-import") (part "C-EUC0603"))
    )
    (comp (ref "C23")
      (value "100n")
      (footprint "eagle-import:C0603")
      (libsource (lib "eagle-import") (part "C-EUC0603"))
    )
    (comp (ref "C24")
      (value "100n")
      (footprint "eagle-import:C0603")
      (libsource (lib "eagle-import") (part "C-EUC0603"))
    )
    (comp (ref "C25")
      (value "100n")
      (footprint "eagle-import:C0603")
      (libsource (lib "eagle-import") (part "C-EUC0603"))
    )
    (comp (ref "C26")
      (value "100n")
      (footprint "eagle-import:C0603")
      (libsource (lib "eagle-import") (part "C-EUC0603"))
    )
    (comp (ref "C27")
      (value "100n")
      (footprint "eagle-import:C0603")
      (libsource (lib "eagle-import") (part "C-EUC0603"))
    )
    (comp (ref "C28")
      (value "100n")
      (footprint "eagle-import:C0603")
      (libsource (lib "eagle-import") (part "C-EUC0603"))
    )
    (comp (ref "C29")
      (value "100n")
      (footprint "eagle-import:C0603")
      (libsource (lib "eagle-import") (part "C-EUC0603"))
    )
    (comp (ref "C30")
      (value "100n")
      (footprint "eagle-import:C0603")
      (libsource (lib "eagle-import") (part "C-EUC0603"))
    )
    (comp (ref "IC8")
      (value "TPS3808G09DBVR")
      (footprint "eagle-import:DBV6")
      (fields
        (field (name "GENERIC_PART_NUMBER") "TPS3808G01")
        (field (name "MANUFACTURER") "Texas Instruments")
        (field (name "MANUFACTURER_PART_NUMBER") "tps3808g01_dbv_6")
        (field (name "DATASHEETURL") "httpwww.ti.comlitgpnTPS3808G01")
        (field (name "FAMILY_NAME") "SUPERVISOR AND RESET IC")
        (field (name "GENERIC_PART_NUMBER_1") "TPS3808G01")
        (field (name "INDUSTRY_STD_PKG_TYPE") "SOT23")
        (field (name "MANUFACTURER_1") "Texas Instruments")
        (field (name "MANUFACTURER_PART_NUMBER_1") "tps3808g01_dbv_6")
        (field (name "PACKAGE_DESIGNATOR") "DBV")
        (field (name "PIN_COUNT") "6")
        (field (name "VENDOR") "Texas Instruments")
      )
      (libsource (lib "eagle-import") (part "TPS3808"))
    )
    (comp (ref "IC9")
      (value "74AUP1G74DC.125")
      (footprint "eagle-import:DCU8")
      (libsource (lib "eagle-import") (part "SN74LVC1G74DCTR-VSSOP"))
    )
    (comp (ref "IC10")
      (value "IS42S16400J")
      (footprint "eagle-import:TSOPII-54")
      (libsource (lib "eagle-import") (part "IS42S16400"))
    )
    (comp (ref "IC11")
      (value "SN74CBTLV3257")
      (footprint "eagle-import:PW(R-PDSO-G16)")
      (libsource (lib "eagle-import") (part "SN74CBTLV3257"))
    )
    (comp (ref "IC12")
      (value "SN74LVC1G02DBVR")
      (footprint "eagle-import:DBV5")
      (libsource (lib "eagle-import") (part "SN74LVC1G02DBVR"))
    )
    (comp (ref "IC13")
      (value "AT25SF041-SSHDT")
      (footprint "eagle-import:SOIC127P600X175-8N")
      (libsource (lib "eagle-import") (part "AT25SFXXX"))
    )
    (comp (ref "IC14")
      (value "SN74CBTLV3257")
      (footprint "eagle-import:PW(R-PDSO-G16)")
      (libsource (lib "eagle-import") (part "SN74CBTLV3257"))
    )
    (comp (ref "R12")
      (value "47K")
      (footprint "eagle-import:R0805")
      (libsource (lib "eagle-import") (part "R-EU_R0805"))
    )
    (comp (ref "R13")
      (value "10K")
      (footprint "eagle-import:R1206")
      (libsource (lib "eagle-import") (part "R-EU_R1206"))
    )
    (comp (ref "R14")
      (value "10K")
      (footprint "eagle-import:R0805")
      (libsource (lib "eagle-import") (part "R-EU_R0805"))
    )
    (comp (ref "R15")
      (value "10K")
      (footprint "eagle-import:R0805")
      (libsource (lib "eagle-import") (part "R-EU_R0805"))
    )
    (comp (ref "R16")
      (value "10K")
      (footprint "eagle-import:R0805")
      (libsource (lib "eagle-import") (part "R-EU_R0805"))
    )
    (comp (ref "R17")
      (value "3K3")
      (footprint "eagle-import:R0805")
      (libsource (lib "eagle-import") (part "R-EU_R0805"))
    )
    (comp (ref "SW1")
      (value "1301.9316")
      (footprint "eagle-import:TACTM-6XN")
      (libsource (lib "eagle-import") (part "TACT_SW"))
    )
    (comp (ref "X2")
      (value "SSW-105-02-S-D")
      (footprint "eagle-import:SSW-105-02-S-D")
      (libsource (lib "eagle-import") (part "SSW-105-02-S-D"))
    )
    (comp (ref "X3")
      (value "TSW-104-02-S-D_NN")
      (footprint "eagle-import:TSW-104-02-S-D-NONUM")
      (libsource (lib "eagle-import") (part "TSW-104-02-S-D_NN"))
    )
    (comp (ref "C58")
      (value "1u")
      (footprint "eagle-import:C0805")
      (libsource (lib "eagle-import") (part "C-EUC0805"))
    )
    (comp (ref "C59")
      (value "470n")
      (footprint "eagle-import:C0805")
      (libsource (lib "eagle-import") (part "C-EUC0805"))
    )
    (comp (ref "C60")
      (value "4n7")
      (footprint "eagle-import:C0805")
      (libsource (lib "eagle-import") (part "C-EUC0805"))
    )
    (comp (ref "C61")
      (value "4n7")
      (footprint "eagle-import:C0805")
      (libsource (lib "eagle-import") (part "C-EUC0805"))
    )
    (comp (ref "C62")
      (value "470n")
      (footprint "eagle-import:C0805")
      (libsource (lib "eagle-import") (part "C-EUC0805"))
    )
    (comp (ref "C63")
      (value "100n")
      (footprint "eagle-import:C0603")
      (libsource (lib "eagle-import") (part "C-EUC0603"))
    )
    (comp (ref "C64")
      (value "220n")
      (footprint "eagle-import:C0805")
      (libsource (lib "eagle-import") (part "C-EUC0805"))
    )
    (comp (ref "C65")
      (value "100n")
      (footprint "eagle-import:C0603")
      (libsource (lib "eagle-import") (part "C-EUC0603"))
    )
    (comp (ref "C66")
      (value "100n")
      (footprint "eagle-import:C0603")
      (libsource (lib "eagle-import") (part "C-EUC0603"))
    )
    (comp (ref "C67")
      (value "100n")
      (footprint "eagle-import:C0603")
      (libsource (lib "eagle-import") (part "C-EUC0603"))
    )
    (comp (ref "C68")
      (value "100n")
      (footprint "eagle-import:C0603")
      (libsource (lib "eagle-import") (part "C-EUC0603"))
    )
    (comp (ref "C69")
      (value "100n")
      (footprint "eagle-import:C0603")
      (libsource (lib "eagle-import") (part "C-EUC0603"))
    )
    (comp (ref "C70")
      (value "100n")
      (footprint "eagle-import:C0603")
      (libsource (lib "eagle-import") (part "C-EUC0603"))
    )
    (comp (ref "C71")
      (value "10u")
      (footprint "eagle-import:EC1206")
      (libsource (lib "eagle-import") (part "ECAP1206"))
    )
    (comp (ref "C72")
      (value "100n")
      (footprint "eagle-import:C0603")
      (libsource (lib "eagle-import") (part "C-EUC0603"))
    )
    (comp (ref "C73")
      (value "100n")
      (footprint "eagle-import:C0603")
      (libsource (lib "eagle-import") (part "C-EUC0603"))
    )
    (comp (ref "C74")
      (value "100n")
      (footprint "eagle-import:C0603")
      (libsource (lib "eagle-import") (part "C-EUC0603"))
    )
    (comp (ref "C75")
      (value "100n")
      (footprint "eagle-import:C0603")
      (libsource (lib "eagle-import") (part "C-EUC0603"))
    )
    (comp (ref "FB3")
      (value "60R@100MHz")
      (footprint "eagle-import:BEAD0603")
      (libsource (lib "eagle-import") (part "FERRITE_BEAD0603"))
    )
    (comp (ref "IC22")
      (value "74LVC1G07SE-7")
      (footprint "eagle-import:DCK5")
      (libsource (lib "eagle-import") (part "SN74LVC1G07-SC70"))
    )
    (comp (ref "IC23")
      (value "TPA6205A1DGN")
      (footprint "eagle-import:SOP65P490X110-9N")
      (libsource (lib "eagle-import") (part "TPA6205"))
    )
    (comp (ref "IC24")
      (value "DP83848CVV/NOPB")
      (footprint "eagle-import:PT48+PAD")
      (libsource (lib "eagle-import") (part "DP83848"))
    )
    (comp (ref "R32")
      (value "20K")
      (footprint "eagle-import:R0805")
      (libsource (lib "eagle-import") (part "R-EU_R0805"))
    )
    (comp (ref "R33")
      (value "1K")
      (footprint "eagle-import:R0805")
      (libsource (lib "eagle-import") (part "R-EU_R0805"))
    )
    (comp (ref "R34")
      (value "1K")
      (footprint "eagle-import:R0805")
      (libsource (lib "eagle-import") (part "R-EU_R0805"))
    )
    (comp (ref "R35")
      (value "10K")
      (footprint "eagle-import:R0805")
      (libsource (lib "eagle-import") (part "R-EU_R0805"))
    )
    (comp (ref "R36")
      (value "10K")
      (footprint "eagle-import:R0805")
      (libsource (lib "eagle-import") (part "R-EU_R0805"))
    )
    (comp (ref "R37")
      (value "47K")
      (footprint "eagle-import:R0805")
      (libsource (lib "eagle-import") (part "R-EU_R0805"))
    )
    (comp (ref "R38")
      (value "20K")
      (footprint "eagle-import:R0805")
      (libsource (lib "eagle-import") (part "R-EU_R0805"))
    )
    (comp (ref "R39")
      (value "33R")
      (footprint "eagle-import:R0603")
      (libsource (lib "eagle-import") (part "R-EU_R0603"))
    )
    (comp (ref "R40")
      (value "49R9")
      (footprint "eagle-import:R0805")
      (libsource (lib "eagle-import") (part "R-EU_R0805"))
    )
    (comp (ref "R41")
      (value "49R9")
      (footprint "eagle-import:R0805")
      (libsource (lib "eagle-import") (part "R-EU_R0805"))
    )
    (comp (ref "R42")
      (value "22R")
      (footprint "eagle-import:R0805")
      (libsource (lib "eagle-import") (part "R-EU_R0805"))
    )
    (comp (ref "R43")
      (value "2K2")
      (footprint "eagle-import:R0805")
      (libsource (lib "eagle-import") (part "R-EU_R0805"))
    )
    (comp (ref "R44")
      (value "49R9")
      (footprint "eagle-import:R0805")
      (libsource (lib "eagle-import") (part "R-EU_R0805"))
    )
    (comp (ref "R45")
      (value "180R")
      (footprint "eagle-import:R0805")
      (libsource (lib "eagle-import") (part "R-EU_R0805"))
    )
    (comp (ref "R46")
      (value "2K2")
      (footprint "eagle-import:R0805")
      (libsource (lib "eagle-import") (part "R-EU_R0805"))
    )
    (comp (ref "R47")
      (value "49R9")
      (footprint "eagle-import:R0805")
      (libsource (lib "eagle-import") (part "R-EU_R0805"))
    )
    (comp (ref "R48")
      (value "2K2")
      (footprint "eagle-import:R0805")
      (libsource (lib "eagle-import") (part "R-EU_R0805"))
    )
    (comp (ref "R49")
      (value "180R")
      (footprint "eagle-import:R0805")
      (libsource (lib "eagle-import") (part "R-EU_R0805"))
    )
    (comp (ref "R50")
      (value "180R")
      (footprint "eagle-import:R0805")
      (libsource (lib "eagle-import") (part "R-EU_R0805"))
    )
    (comp (ref "R51")
      (value "2K2")
      (footprint "eagle-import:R0805")
      (libsource (lib "eagle-import") (part "R-EU_R0805"))
    )
    (comp (ref "R52")
      (value "2K2")
      (footprint "eagle-import:R0805")
      (libsource (lib "eagle-import") (part "R-EU_R0805"))
    )
    (comp (ref "R53")
      (value "4K87")
      (footprint "eagle-import:R0603")
      (libsource (lib "eagle-import") (part "R-EU_R0603"))
    )
    (comp (ref "SP1")
      (value "LD-BZEN-0803")
      (footprint "eagle-import:LD-BZEN-0803")
      (libsource (lib "eagle-import") (part "BUZZER-0803"))
    )
    (comp (ref "SPEED")
      (value "HSMY-C170")
      (footprint "eagle-import:LED_0805")
      (libsource (lib "eagle-import") (part "LED0805"))
    )
    (comp (ref "X6")
      (value "22-23-2021")
      (footprint "eagle-import:22-23-2021")
      (fields
        (field (name "MF") "MOLEX")
        (field (name "MPN") "22-23-2021")
        (field (name "OC_FARNELL") "1462926")
        (field (name "OC_NEWARK") "25C3832")
      )
      (libsource (lib "eagle-import") (part "22-23-2021"))
    )
    (comp (ref "X7")
      (value "LMJTAB881243M-L")
      (footprint "eagle-import:RJ45-TRAFO-LED")
      (libsource (lib "eagle-import") (part "RJ45-TRAFO-LED"))
    )
    (comp (ref "XO2")
      (value "CFPS-73-25M")
      (footprint "eagle-import:12SMX(C)")
      (libsource (lib "eagle-import") (part "XO-7X5MM"))
    )
  )
  (nets
    (net (code "5") (name "+1V0") (class "Default")
      (node (ref "C46") (pin "1") (pinfunction "1_1") (pintype "passive"))
      (node (ref "C47") (pin "1") (pinfunction "1_1") (pintype "passive"))
      (node (ref "C48") (pin "1") (pinfunction "1_1") (pintype "passive"))
      (node (ref "C49") (pin "1") (pinfunction "1_1") (pintype "passive"))
      (node (ref "C50") (pin "1") (pinfunction "1_1") (pintype "passive"))
      (node (ref "C52") (pin "1") (pinfunction "1_1") (pintype "passive"))
      (node (ref "C53") (pin "1") (pinfunction "1_1") (pintype "passive"))
      (node (ref "C54") (pin "1") (pinfunction "1_1") (pintype "passive"))
      (node (ref "C55") (pin "1") (pinfunction "1_1") (pintype "passive"))
      (node (ref "C56") (pin "1") (pinfunction "1_1") (pintype "passive"))
      (node (ref "C9") (pin "1") (pinfunction "1_1") (pintype "passive"))
      (node (ref "IC18") (pin "101") (pinfunction "VDD-101_101") (pintype "power_in"))
      (node (ref "IC18") (pin "102") (pinfunction "VDD-102_102") (pintype "power_in"))
      (node (ref "IC18") (pin "11") (pinfunction "VDD-11_11") (pintype "power_in"))
      (node (ref "IC18") (pin "120") (pinfunction "VDD-120_120") (pintype "power_in"))
      (node (ref "IC18") (pin "126") (pinfunction "VDD-126_126") (pintype "power_in"))
      (node (ref "IC18") (pin "16") (pinfunction "VDD-16_16") (pintype "power_in"))
      (node (ref "IC18") (pin "17") (pinfunction "VDD-17_17") (pintype "power_in"))
      (node (ref "IC18") (pin "24") (pinfunction "VDD-24_24") (pintype "power_in"))
      (node (ref "IC18") (pin "36") (pinfunction "VDD-36_36") (pintype "power_in"))
      (node (ref "IC18") (pin "41") (pinfunction "VDD-41_41") (pintype "power_in"))
      (node (ref "IC18") (pin "49") (pinfunction "USB_VDD_49") (pintype "power_in"))
      (node (ref "IC18") (pin "56") (pinfunction "VDD-56_56") (pintype "power_in"))
      (node (ref "IC18") (pin "60") (pinfunction "VDD-60_60") (pintype "power_in"))
      (node (ref "IC18") (pin "73") (pinfunction "VDD-73_73") (pintype "power_in"))
      (node (ref "IC18") (pin "80") (pinfunction "VDD-80_80") (pintype "power_in"))
      (node (ref "IC18") (pin "81") (pinfunction "VDD-81_81") (pintype "power_in"))
      (node (ref "IC18") (pin "87") (pinfunction "VDD-87_87") (pintype "power_in"))
      (node (ref "IC8") (pin "5") (pinfunction "SENSE_5") (pintype "passive"))
      (node (ref "L3") (pin "2") (pinfunction "2_2") (pintype "passive"))
      (node (ref "R31") (pin "1") (pinfunction "1_1") (pintype "passive"))
      (node (ref "R8") (pin "2") (pinfunction "2_2") (pintype "passive"))
    )
    (net (code "6") (name "+3V3") (class "Default")
      (node (ref "C10") (pin "2") (pinfunction "2_2") (pintype "passive"))
      (node (ref "C11") (pin "2") (pinfunction "2_2") (pintype "passive"))
      (node (ref "C12") (pin "2") (pinfunction "2_2") (pintype "passive"))
      (node (ref "C13") (pin "2") (pinfunction "2_2") (pintype "passive"))
      (node (ref "C17") (pin "1") (pinfunction "1_1") (pintype "passive"))
      (node (ref "C19") (pin "1") (pinfunction "1_1") (pintype "passive"))
      (node (ref "C2") (pin "1") (pinfunction "1_1") (pintype "passive"))
      (node (ref "C21") (pin "1") (pinfunction "1_1") (pintype "passive"))
      (node (ref "C22") (pin "1") (pinfunction "1_1") (pintype "passive"))
      (node (ref "C23") (pin "1") (pinfunction "1_1") (pintype "passive"))
      (node (ref "C24") (pin "1") (pinfunction "1_1") (pintype "passive"))
      (node (ref "C25") (pin "1") (pinfunction "1_1") (pintype "passive"))
      (node (ref "C26") (pin "1") (pinfunction "1_1") (pintype "passive"))
      (node (ref "C27") (pin "1") (pinfunction "1_1") (pintype "passive"))
      (node (ref "C28") (pin "1") (pinfunction "1_1") (pintype "passive"))
      (node (ref "C29") (pin "1") (pinfunction "1_1") (pintype "passive"))
      (node (ref "C30") (pin "1") (pinfunction "1_1") (pintype "passive"))
      (node (ref "C35") (pin "1") (pinfunction "1_1") (pintype "passive"))
      (node (ref "C36") (pin "1") (pinfunction "1_1") (pintype "passive"))
      (node (ref "C37") (pin "1") (pinfunction "1_1") (pintype "passive"))
      (node (ref "C38") (pin "1") (pinfunction "1_1") (pintype "passive"))
      (node (ref "C39") (pin "1") (pinfunction "1_1") (pintype "passive"))
      (node (ref "C42") (pin "1") (pinfunction "1_1") (pintype "passive"))
      (node (ref "C43") (pin "1") (pinfunction "1_1") (pintype "passive"))
      (node (ref "C44") (pin "1") (pinfunction "1_1") (pintype "passive"))
      (node (ref "C45") (pin "1") (pinfunction "1_1") (pintype "passive"))
      (node (ref "C5") (pin "1") (pinfunction "1_1") (pintype "passive"))
      (node (ref "C51") (pin "1") (pinfunction "1_1") (pintype "passive"))
      (node (ref "C58") (pin "2") (pinfunction "2_2") (pintype "passive"))
      (node (ref "C6") (pin "2") (pinfunction "2_2") (pintype "passive"))
      (node (ref "C63") (pin "2") (pinfunction "2_2") (pintype "passive"))
      (node (ref "C74") (pin "1") (pinfunction "1_1") (pintype "passive"))
      (node (ref "C75") (pin "1") (pinfunction "1_1") (pintype "passive"))
      (node (ref "C76") (pin "1") (pinfunction "1_1") (pintype "passive"))
      (node (ref "C77") (pin "1") (pinfunction "1_1") (pintype "passive"))
      (node (ref "C80") (pin "2") (pinfunction "2_2") (pintype "passive"))
      (node (ref "C81") (pin "1") (pinfunction "1_1") (pintype "passive"))
      (node (ref "D2") (pin "A") (pinfunction "A_A") (pintype "passive"))
      (node (ref "FB3") (pin "P$1") (pinfunction "1_P$1") (pintype "passive"))
      (node (ref "IC10") (pin "1") (pinfunction "VDD-1_1") (pintype "power_in"))
      (node (ref "IC10") (pin "14") (pinfunction "VDD-14_14") (pintype "power_in"))
      (node (ref "IC10") (pin "27") (pinfunction "VDD-27_27") (pintype "power_in"))
      (node (ref "IC10") (pin "3") (pinfunction "VDDQ-3_3") (pintype "power_in"))
      (node (ref "IC10") (pin "43") (pinfunction "VDDQ-43_43") (pintype "power_in"))
      (node (ref "IC10") (pin "49") (pinfunction "VDDQ-49_49") (pintype "power_in"))
      (node (ref "IC10") (pin "9") (pinfunction "VDDQ-9_9") (pintype "power_in"))
      (node (ref "IC11") (pin "16") (pinfunction "VCC_16") (pintype "power_in"))
      (node (ref "IC12") (pin "5") (pinfunction "VDD_5") (pintype "power_in"))
      (node (ref "IC13") (pin "8") (pinfunction "VCC_8") (pintype "power_in"))
      (node (ref "IC14") (pin "16") (pinfunction "VCC_16") (pintype "power_in"))
      (node (ref "IC18") (pin "105") (pinfunction "OTP_VCC_105") (pintype "power_in"))
      (node (ref "IC18") (pin "110") (pinfunction "VDDIOT-110_110") (pintype "power_in"))
      (node (ref "IC18") (pin "111") (pinfunction "VDDIOT-111_111") (pintype "power_in"))
      (node (ref "IC18") (pin "14") (pinfunction "VDDIOL-14_14") (pintype "power_in"))
      (node (ref "IC18") (pin "19") (pinfunction "VDDIOL-19_19") (pintype "power_in"))
      (node (ref "IC18") (pin "29") (pinfunction "VDDIOL-29_29") (pintype "power_in"))
      (node (ref "IC18") (pin "42") (pinfunction "VDDIOL-42_42") (pintype "power_in"))
      (node (ref "IC18") (pin "44") (pinfunction "USB_VDD33_44") (pintype "power_in"))
      (node (ref "IC18") (pin "52") (pinfunction "VDDIOR-52_52") (pintype "power_in"))
      (node (ref "IC18") (pin "6") (pinfunction "VDDIOL-6_6") (pintype "power_in"))
      (node (ref "IC18") (pin "67") (pinfunction "VDDIOR-67_67") (pintype "power_in"))
      (node (ref "IC18") (pin "78") (pinfunction "VDDIOR-78_78") (pintype "power_in"))
      (node (ref "IC18") (pin "83") (pinfunction "VDDIOR-83_83") (pintype "power_in"))
      (node (ref "IC18") (pin "92") (pinfunction "VDDIOR-92_92") (pintype "power_in"))
      (node (ref "IC19") (pin "6") (pinfunction "VCC_6") (pintype "passive"))
      (node (ref "IC20") (pin "6") (pinfunction "VCC_6") (pintype "passive"))
      (node (ref "IC21") (pin "5") (pinfunction "VDD_5") (pintype "power_in"))
      (node (ref "IC22") (pin "5") (pinfunction "VDD_5") (pintype "power_in"))
      (node (ref "IC23") (pin "6") (pinfunction "VDD_6") (pintype "power_in"))
      (node (ref "IC24") (pin "32") (pinfunction "IOVDD33-32_32") (pintype "power_in"))
      (node (ref "IC24") (pin "48") (pinfunction "IOVDD33-48_48") (pintype "power_in"))
      (node (ref "IC26") (pin "10") (pinfunction "~{SRCLR}_10") (pintype "input"))
      (node (ref "IC26") (pin "16") (pinfunction "VCC_16") (pintype "power_in"))
      (node (ref "IC28") (pin "9") (pinfunction "VDD_9") (pintype "power_in"))
      (node (ref "IC29") (pin "3") (pinfunction "~{WP}_3") (pintype "input"))
      (node (ref "IC29") (pin "7") (pinfunction "~{HOLD}_7") (pintype "input"))
      (node (ref "IC29") (pin "8") (pinfunction "VCC_8") (pintype "power_in"))
      (node (ref "IC3") (pin "10") (pinfunction "~{SRCLR}_10") (pintype "input"))
      (node (ref "IC3") (pin "16") (pinfunction "VCC_16") (pintype "power_in"))
      (node (ref "IC5") (pin "10") (pinfunction "~{SRCLR}_10") (pintype "input"))
      (node (ref "IC5") (pin "16") (pinfunction "VCC_16") (pintype "power_in"))
      (node (ref "IC6") (pin "5") (pinfunction "SENSE_5") (pintype "passive"))
      (node (ref "IC6") (pin "6") (pinfunction "VDD_6") (pintype "power_in"))
      (node (ref "IC7") (pin "1") (pinfunction "VDD_1") (pintype "power_in"))
      (node (ref "IC8") (pin "6") (pinfunction "VDD_6") (pintype "power_in"))
      (node (ref "IC9") (pin "2") (pinfunction "D_2") (pintype "input"))
      (node (ref "IC9") (pin "7") (pinfunction "~{PRE}_7") (pintype "input"))
      (node (ref "IC9") (pin "8") (pinfunction "VDD_8") (pintype "power_in"))
      (node (ref "J2") (pin "3") (pinfunction "CMD_3") (pintype "passive"))
      (node (ref "L1") (pin "1") (pinfunction "1_1") (pintype "passive"))
      (node (ref "L2") (pin "2") (pinfunction "2_2") (pintype "passive"))
      (node (ref "LCD1") (pin "4") (pinfunction "VDD_4") (pintype "power_in"))
      (node (ref "MOD1") (pin "1") (pinfunction "3V3_1") (pintype "power_in"))
      (node (ref "PWR_3V3") (pin "A") (pinfunction "A_A") (pintype "passive"))
      (node (ref "R1") (pin "1") (pinfunction "1_1") (pintype "passive"))
      (node (ref "R10") (pin "2") (pinfunction "2_2") (pintype "passive"))
      (node (ref "R12") (pin "1") (pinfunction "1_1") (pintype "passive"))
      (node (ref "R13") (pin "1") (pinfunction "1_1") (pintype "passive"))
      (node (ref "R14") (pin "1") (pinfunction "1_1") (pintype "passive"))
      (node (ref "R16") (pin "2") (pinfunction "2_2") (pintype "passive"))
      (node (ref "R17") (pin "2") (pinfunction "2_2") (pintype "passive"))
      (node (ref "R19") (pin "2") (pinfunction "2_2") (pintype "passive"))
      (node (ref "R20") (pin "1") (pinfunction "1_1") (pintype "passive"))
      (node (ref "R26") (pin "1") (pinfunction "1_1") (pintype "passive"))
      (node (ref "R4") (pin "2") (pinfunction "2_2") (pintype "passive"))
      (node (ref "R43") (pin "1") (pinfunction "1_1") (pintype "passive"))
      (node (ref "R45") (pin "1") (pinfunction "1_1") (pintype "passive"))
      (node (ref "R46") (pin "1") (pinfunction "1_1") (pintype "passive"))
      (node (ref "R48") (pin "1") (pinfunction "1_1") (pintype "passive"))
      (node (ref "R65") (pin "2") (pinfunction "2_2") (pintype "passive"))
      (node (ref "R66") (pin "2") (pinfunction "2_2") (pintype "passive"))
      (node (ref "R7") (pin "2") (pinfunction "2_2") (pintype "passive"))
      (node (ref "X3") (pin "7") (pinfunction "1_7") (pintype "passive"))
      (node (ref "X4") (pin "5") (pinfunction "1_5") (pintype "passive"))
      (node (ref "X7") (pin "12") (pinfunction "YELLOW_A_12") (pintype "passive"))
      (node (ref "X7") (pin "9") (pinfunction "GREEN-A_9") (pintype "passive"))
      (node (ref "X9") (pin "1") (pinfunction "1_1") (pintype "passive"))
      (node (ref "X9") (pin "17") (pinfunction "1_17") (pintype "passive"))
      (node (ref "X9") (pin "18") (pinfunction "1_18") (pintype "passive"))
      (node (ref "XO1") (pin "4") (pinfunction "VDD_4") (pintype "power_in"))
      (node (ref "XO2") (pin "4") (pinfunction "VDD_4") (pintype "power_in"))
    )
    (net (code "7") (name "+3V3(A)") (class "Default")
      (node (ref "C66") (pin "2") (pinfunction "2_2") (pintype "passive"))
      (node (ref "C68") (pin "2") (pinfunction "2_2") (pintype "passive"))
      (node (ref "C73") (pin "1") (pinfunction "1_1") (pintype "passive"))
      (node (ref "FB3") (pin "P$2") (pinfunction "2_P$2") (pintype "passive"))
      (node (ref "IC24") (pin "22") (pinfunction "AVDD33_22") (pintype "power_in"))
      (node (ref "X7") (pin "3") (pinfunction "CT_3") (pintype "input"))
      (node (ref "X7") (pin "6") (pinfunction "CR_6") (pintype "input"))
    )
    (net (code "8") (name "+5V") (class "Default")
      (node (ref "C41") (pin "1") (pinfunction "1_1") (pintype "passive"))
      (node (ref "IC15") (pin "5") (pinfunction "IN_5") (pintype "input"))
      (node (ref "L4") (pin "2") (pinfunction "2_2") (pintype "passive"))
      (node (ref "R23") (pin "2") (pinfunction "2_2") (pintype "passive"))
      (node (ref "X4") (pin "6") (pinfunction "1_6") (pintype "passive"))
    )
    (net (code "12") (name "1V0_EN") (class "Default")
      (node (ref "IC4") (pin "5") (pinfunction "EN_5") (pintype "input"))
      (node (ref "IC6") (pin "1") (pinfunction "~{RESET}_1") (pintype "output"))
      (node (ref "R10") (pin "1") (pinfunction "1_1") (pintype "passive"))
    )
    (net (code "13") (name "3") (class "Default")
      (node (ref "X1") (pin "3") (pinfunction "3_3") (pintype "power_in"))
    )
    (net (code "14") (name "5V0") (class "Default")
      (node (ref "MOD1") (pin "6") (pinfunction "5V0_6") (pintype "power_in"))
    )
    (net (code "15") (name "AUDIO_OUT") (class "Default")
      (node (ref "IC18") (pin "62") (pinfunction "X0D12_62") (pintype "bidirectional"))
      (node (ref "IC22") (pin "2") (pinfunction "A_2") (pintype "input"))
      (node (ref "X9") (pin "10") (pinfunction "1_10") (pintype "passive"))
    )
    (net (code "16") (name "ETH_MDC") (class "Default")
      (node (ref "IC18") (pin "122") (pinfunction "X1D11_122") (pintype "bidirectional"))
      (node (ref "IC24") (pin "31") (pinfunction "MDC_31") (pintype "input"))
    )
    (net (code "17") (name "ETH_MDIO") (class "Default")
      (node (ref "IC18") (pin "121") (pinfunction "X1D10_121") (pintype "bidirectional"))
      (node (ref "IC24") (pin "30") (pinfunction "MDIO_30") (pintype "bidirectional"))
    )
    (net (code "18") (name "ETH_RST") (class "Default")
      (node (ref "IC18") (pin "18") (pinfunction "X1D37_18") (pintype "bidirectional"))
      (node (ref "IC24") (pin "29") (pinfunction "RESET_N_29") (pintype "input"))
      (node (ref "MOD1") (pin "8") (pinfunction "RST_8") (pintype "passive"))
    )
    (net (code "19") (name "ETH_RX0") (class "Default")
      (node (ref "IC18") (pin "116") (pinfunction "X1D30_116") (pintype "bidirectional"))
      (node (ref "IC24") (pin "43") (pinfunction "PHYAD1(RXD1_0)_43") (pintype "output"))
    )
    (net (code "20") (name "ETH_RX1") (class "Default")
      (node (ref "IC18") (pin "117") (pinfunction "X1D31_117") (pintype "bidirectional"))
      (node (ref "IC24") (pin "44") (pinfunction "PHYAD2(RXD1_1)_44") (pintype "output"))
    )
    (net (code "21") (name "ETH_RX2") (class "Default")
      (node (ref "IC18") (pin "118") (pinfunction "X1D32_118") (pintype "bidirectional"))
      (node (ref "IC24") (pin "45") (pinfunction "PHYAD3(RXD1_2)_45") (pintype "output"))
    )
    (net (code "22") (name "ETH_RX3") (class "Default")
      (node (ref "IC18") (pin "119") (pinfunction "X1D33_119") (pintype "bidirectional"))
      (node (ref "IC24") (pin "46") (pinfunction "PHYAD4(RXD1_3)_46") (pintype "output"))
    )
    (net (code "23") (name "ETH_RX_CLK") (class "Default")
      (node (ref "IC18") (pin "114") (pinfunction "X1D28_114") (pintype "bidirectional"))
      (node (ref "IC24") (pin "38") (pinfunction "RX_CLK_38") (pintype "output"))
    )
    (net (code "24") (name "ETH_RX_CTL") (class "Default")
      (node (ref "IC18") (pin "115") (pinfunction "X1D29_115") (pintype "bidirectional"))
      (node (ref "IC24") (pin "39") (pinfunction "MII_MODE(RX_DV)_39") (pintype "output"))
    )
    (net (code "25") (name "ETH_RX_ER") (class "Default")
      (node (ref "IC18") (pin "15") (pinfunction "X1D36_15") (pintype "bidirectional"))
      (node (ref "IC24") (pin "41") (pinfunction "MDIX_EN(RX_ER)_41") (pintype "output"))
    )
    (net (code "26") (name "ETH_TX0") (class "Default")
      (node (ref "IC18") (pin "109") (pinfunction "X1D43_109") (pintype "bidirectional"))
      (node (ref "IC24") (pin "3") (pinfunction "TXD_0_3") (pintype "input"))
    )
    (net (code "27") (name "ETH_TX1") (class "Default")
      (node (ref "IC18") (pin "108") (pinfunction "X1D42_108") (pintype "bidirectional"))
      (node (ref "IC24") (pin "4") (pinfunction "TXD_1_4") (pintype "input"))
    )
    (net (code "28") (name "ETH_TX2") (class "Default")
      (node (ref "IC18") (pin "107") (pinfunction "X1D41_107") (pintype "bidirectional"))
      (node (ref "IC24") (pin "5") (pinfunction "TXD_2_5") (pintype "input"))
    )
    (net (code "29") (name "ETH_TX3") (class "Default")
      (node (ref "IC18") (pin "106") (pinfunction "X1D40_106") (pintype "bidirectional"))
      (node (ref "IC24") (pin "6") (pinfunction "TXD_3/SNI_MODE_6") (pintype "input"))
    )
    (net (code "30") (name "ETH_TX_CLK") (class "Default")
      (node (ref "IC24") (pin "1") (pinfunction "TX_CLK_1") (pintype "output"))
      (node (ref "R42") (pin "2") (pinfunction "2_2") (pintype "passive"))
    )
    (net (code "31") (name "ETH_TX_CTL") (class "Default")
      (node (ref "IC18") (pin "113") (pinfunction "X1D27_113") (pintype "bidirectional"))
      (node (ref "IC24") (pin "2") (pinfunction "TX_EN_2") (pintype "input"))
    )
    (net (code "32") (name "GND") (class "Default")
      (node (ref "C1") (pin "2") (pinfunction "2_2") (pintype "passive"))
      (node (ref "C10") (pin "1") (pinfunction "1_1") (pintype "passive"))
      (node (ref "C11") (pin "1") (pinfunction "1_1") (pintype "passive"))
      (node (ref "C12") (pin "1") (pinfunction "1_1") (pintype "passive"))
      (node (ref "C13") (pin "1") (pinfunction "1_1") (pintype "passive"))
      (node (ref "C14") (pin "2") (pinfunction "2_2") (pintype "passive"))
      (node (ref "C15") (pin "2") (pinfunction "2_2") (pintype "passive"))
      (node (ref "C16") (pin "2") (pinfunction "2_2") (pintype "passive"))
      (node (ref "C17") (pin "2") (pinfunction "2_2") (pintype "passive"))
      (node (ref "C18") (pin "1") (pinfunction "1_1") (pintype "passive"))
      (node (ref "C19") (pin "2") (pinfunction "2_2") (pintype "passive"))
      (node (ref "C2") (pin "2") (pinfunction "2_2") (pintype "passive"))
      (node (ref "C20") (pin "2") (pinfunction "2_2") (pintype "passive"))
      (node (ref "C21") (pin "2") (pinfunction "2_2") (pintype "passive"))
      (node (ref "C22") (pin "2") (pinfunction "2_2") (pintype "passive"))
      (node (ref "C23") (pin "2") (pinfunction "2_2") (pintype "passive"))
      (node (ref "C24") (pin "2") (pinfunction "2_2") (pintype "passive"))
      (node (ref "C25") (pin "2") (pinfunction "2_2") (pintype "passive"))
      (node (ref "C26") (pin "2") (pinfunction "2_2") (pintype "passive"))
      (node (ref "C27") (pin "2") (pinfunction "2_2") (pintype "passive"))
      (node (ref "C28") (pin "2") (pinfunction "2_2") (pintype "passive"))
      (node (ref "C29") (pin "2") (pinfunction "2_2") (pintype "passive"))
      (node (ref "C30") (pin "2") (pinfunction "2_2") (pintype "passive"))
      (node (ref "C31") (pin "2") (pinfunction "2_2") (pintype "passive"))
      (node (ref "C32") (pin "2") (pinfunction "2_2") (pintype "passive"))
      (node (ref "C33") (pin "1") (pinfunction "1_1") (pintype "passive"))
      (node (ref "C35") (pin "2") (pinfunction "2_2") (pintype "passive"))
      (node (ref "C36") (pin "2") (pinfunction "2_2") (pintype "passive"))
      (node (ref "C37") (pin "2") (pinfunction "2_2") (pintype "passive"))
      (node (ref "C38") (pin "2") (pinfunction "2_2") (pintype "passive"))
      (node (ref "C39") (pin "2") (pinfunction "2_2") (pintype "passive"))
      (node (ref "C4") (pin "2") (pinfunction "2_2") (pintype "passive"))
      (node (ref "C40") (pin "2") (pinfunction "2_2") (pintype "passive"))
      (node (ref "C41") (pin "2") (pinfunction "2_2") (pintype "passive"))
      (node (ref "C42") (pin "2") (pinfunction "2_2") (pintype "passive"))
      (node (ref "C43") (pin "2") (pinfunction "2_2") (pintype "passive"))
      (node (ref "C44") (pin "2") (pinfunction "2_2") (pintype "passive"))
      (node (ref "C45") (pin "2") (pinfunction "2_2") (pintype "passive"))
      (node (ref "C46") (pin "2") (pinfunction "2_2") (pintype "passive"))
      (node (ref "C47") (pin "2") (pinfunction "2_2") (pintype "passive"))
      (node (ref "C48") (pin "2") (pinfunction "2_2") (pintype "passive"))
      (node (ref "C49") (pin "2") (pinfunction "2_2") (pintype "passive"))
      (node (ref "C5") (pin "2") (pinfunction "2_2") (pintype "passive"))
      (node (ref "C50") (pin "2") (pinfunction "2_2") (pintype "passive"))
      (node (ref "C51") (pin "2") (pinfunction "2_2") (pintype "passive"))
      (node (ref "C52") (pin "2") (pinfunction "2_2") (pintype "passive"))
      (node (ref "C53") (pin "2") (pinfunction "2_2") (pintype "passive"))
      (node (ref "C54") (pin "2") (pinfunction "2_2") (pintype "passive"))
      (node (ref "C55") (pin "2") (pinfunction "2_2") (pintype "passive"))
      (node (ref "C56") (pin "2") (pinfunction "2_2") (pintype "passive"))
      (node (ref "C57") (pin "2") (pinfunction "2_2") (pintype "passive"))
      (node (ref "C58") (pin "1") (pinfunction "1_1") (pintype "passive"))
      (node (ref "C59") (pin "2") (pinfunction "2_2") (pintype "passive"))
      (node (ref "C6") (pin "1") (pinfunction "1_1") (pintype "passive"))
      (node (ref "C60") (pin "2") (pinfunction "2_2") (pintype "passive"))
      (node (ref "C61") (pin "2") (pinfunction "2_2") (pintype "passive"))
      (node (ref "C63") (pin "1") (pinfunction "1_1") (pintype "passive"))
      (node (ref "C64") (pin "1") (pinfunction "1_1") (pintype "passive"))
      (node (ref "C65") (pin "2") (pinfunction "2_2") (pintype "passive"))
      (node (ref "C66") (pin "1") (pinfunction "1_1") (pintype "passive"))
      (node (ref "C67") (pin "2") (pinfunction "2_2") (pintype "passive"))
      (node (ref "C68") (pin "1") (pinfunction "1_1") (pintype "passive"))
      (node (ref "C69") (pin "2") (pinfunction "2_2") (pintype "passive"))
      (node (ref "C70") (pin "2") (pinfunction "2_2") (pintype "passive"))
      (node (ref "C71") (pin "-") (pinfunction "-_-") (pintype "passive"))
      (node (ref "C72") (pin "2") (pinfunction "2_2") (pintype "passive"))
      (node (ref "C73") (pin "2") (pinfunction "2_2") (pintype "passive"))
      (node (ref "C74") (pin "2") (pinfunction "2_2") (pintype "passive"))
      (node (ref "C75") (pin "2") (pinfunction "2_2") (pintype "passive"))
      (node (ref "C76") (pin "2") (pinfunction "2_2") (pintype "passive"))
      (node (ref "C77") (pin "2") (pinfunction "2_2") (pintype "passive"))
      (node (ref "C78") (pin "1") (pinfunction "1_1") (pintype "passive"))
      (node (ref "C79") (pin "2") (pinfunction "-_2") (pintype "passive"))
      (node (ref "C8") (pin "2") (pinfunction "2_2") (pintype "passive"))
      (node (ref "C80") (pin "1") (pinfunction "1_1") (pintype "passive"))
      (node (ref "C81") (pin "2") (pinfunction "2_2") (pintype "passive"))
      (node (ref "C9") (pin "2") (pinfunction "2_2") (pintype "passive"))
      (node (ref "FB2") (pin "P$1") (pinfunction "1_P$1") (pintype "passive"))
      (node (ref "IC1") (pin "2") (pinfunction "GND_2") (pintype "power_in"))
      (node (ref "IC10") (pin "12") (pinfunction "GNDQ-12_12") (pintype "power_in"))
      (node (ref "IC10") (pin "28") (pinfunction "GND-28_28") (pintype "power_in"))
      (node (ref "IC10") (pin "41") (pinfunction "GND_41") (pintype "power_in"))
      (node (ref "IC10") (pin "46") (pinfunction "GNDQ-46_46") (pintype "power_in"))
      (node (ref "IC10") (pin "52") (pinfunction "GNDQ-52_52") (pintype "power_in"))
      (node (ref "IC10") (pin "54") (pinfunction "GND-54_54") (pintype "power_in"))
      (node (ref "IC10") (pin "6") (pinfunction "GNDQ-6_6") (pintype "power_in"))
      (node (ref "IC11") (pin "12") (pinfunction "4A_12") (pintype "passive"))
      (node (ref "IC11") (pin "15") (pinfunction "~{OE}_15") (pintype "bidirectional"))
      (node (ref "IC11") (pin "8") (pinfunction "GND_8") (pintype "power_in"))
      (node (ref "IC12") (pin "3") (pinfunction "VSS_3") (pintype "power_in"))
      (node (ref "IC13") (pin "4") (pinfunction "GND_4") (pintype "power_in"))
      (node (ref "IC14") (pin "15") (pinfunction "~{OE}_15") (pintype "bidirectional"))
      (node (ref "IC14") (pin "8") (pinfunction "GND_8") (pintype "power_in"))
      (node (ref "IC15") (pin "2") (pinfunction "GND_2") (pintype "power_in"))
      (node (ref "IC16") (pin "1") (pinfunction "GND_1") (pintype "passive"))
      (node (ref "IC17") (pin "1") (pinfunction "GND_1") (pintype "power_in"))
      (node (ref "IC18") (pin "104") (pinfunction "PLL_AGND_104") (pintype "power_in"))
      (node (ref "IC18") (pin "PAD") (pinfunction "VSS_PAD") (pintype "power_in"))
      (node (ref "IC19") (pin "3") (pinfunction "GND_3") (pintype "power_in"))
      (node (ref "IC2") (pin "1") (pinfunction "GND_1") (pintype "power_in"))
      (node (ref "IC20") (pin "3") (pinfunction "GND_3") (pintype "power_in"))
      (node (ref "IC21") (pin "3") (pinfunction "VSS_3") (pintype "power_in"))
      (node (ref "IC22") (pin "3") (pinfunction "VSS_3") (pintype "power_in"))
      (node (ref "IC23") (pin "7") (pinfunction "GND_7") (pintype "passive"))
      (node (ref "IC23") (pin "TP") (pinfunction "TP_TP") (pintype "passive"))
      (node (ref "IC24") (pin "15") (pinfunction "AGND-15_15") (pintype "power_in"))
      (node (ref "IC24") (pin "19") (pinfunction "AGND-19_19") (pintype "power_in"))
      (node (ref "IC24") (pin "35") (pinfunction "IOGND-35_35") (pintype "power_in"))
      (node (ref "IC24") (pin "36") (pinfunction "DGND_36") (pintype "power_in"))
      (node (ref "IC24") (pin "47") (pinfunction "IOGND-47_47") (pintype "power_in"))
      (node (ref "IC24") (pin "PAD") (pinfunction "GND_PAD") (pintype "power_in"))
      (node (ref "IC26") (pin "13") (pinfunction "~{OE}_13") (pintype "input"))
      (node (ref "IC26") (pin "8") (pinfunction "GND_8") (pintype "power_in"))
      (node (ref "IC27") (pin "7") (pinfunction "VSS_7") (pintype "passive"))
      (node (ref "IC28") (pin "10") (pinfunction "VSS_10") (pintype "power_in"))
      (node (ref "IC28") (pin "15") (pinfunction "A0_15") (pintype "input"))
      (node (ref "IC28") (pin "16") (pinfunction "A1_16") (pintype "input"))
      (node (ref "IC28") (pin "17") (pinfunction "A2_17") (pintype "input"))
      (node (ref "IC29") (pin "4") (pinfunction "GND_4") (pintype "passive"))
      (node (ref "IC3") (pin "13") (pinfunction "~{OE}_13") (pintype "input"))
      (node (ref "IC3") (pin "8") (pinfunction "GND_8") (pintype "power_in"))
      (node (ref "IC4") (pin "1") (pinfunction "GND_1") (pintype "power_in"))
      (node (ref "IC5") (pin "13") (pinfunction "~{OE}_13") (pintype "input"))
      (node (ref "IC5") (pin "8") (pinfunction "GND_8") (pintype "power_in"))
      (node (ref "IC6") (pin "2") (pinfunction "GND_2") (pintype "power_in"))
      (node (ref "IC7") (pin "14") (pinfunction "SX+_14") (pintype "bidirectional"))
      (node (ref "IC7") (pin "17") (pinfunction "5WSX-_17") (pintype "input"))
      (node (ref "IC7") (pin "2") (pinfunction "M1_2") (pintype "bidirectional"))
      (node (ref "IC7") (pin "20") (pinfunction "VSS_20") (pintype "power_in"))
      (node (ref "IC7") (pin "3") (pinfunction "SY-_3") (pintype "bidirectional"))
      (node (ref "IC7") (pin "7") (pinfunction "SY+_7") (pintype "bidirectional"))
      (node (ref "IC8") (pin "2") (pinfunction "GND_2") (pintype "power_in"))
      (node (ref "IC9") (pin "4") (pinfunction "VSS_4") (pintype "power_in"))
      (node (ref "J1") (pin "5") (pinfunction "GND_5") (pintype "passive"))
      (node (ref "J2") (pin "5") (pinfunction "CLK_5") (pintype "passive"))
      (node (ref "J2") (pin "S") (pinfunction "SH_S") (pintype "passive"))
      (node (ref "J2") (pin "SW2") (pinfunction "SW2_SW2") (pintype "passive"))
      (node (ref "LCD1") (pin "13") (pinfunction "G0_13") (pintype "input"))
      (node (ref "LCD1") (pin "14") (pinfunction "G1_14") (pintype "input"))
      (node (ref "LCD1") (pin "21") (pinfunction "B0_21") (pintype "input"))
      (node (ref "LCD1") (pin "22") (pinfunction "B1_22") (pintype "input"))
      (node (ref "LCD1") (pin "23") (pinfunction "B2_23") (pintype "input"))
      (node (ref "LCD1") (pin "29") (pinfunction "GND-29_29") (pintype "power_in"))
      (node (ref "LCD1") (pin "3") (pinfunction "GND-3_3") (pintype "power_in"))
      (node (ref "LCD1") (pin "5") (pinfunction "R0_5") (pintype "input"))
      (node (ref "LCD1") (pin "6") (pinfunction "R1_6") (pintype "input"))
      (node (ref "LCD1") (pin "7") (pinfunction "R2_7") (pintype "input"))
      (node (ref "MOD1") (pin "7") (pinfunction "GND_7") (pintype "power_in"))
      (node (ref "OK1") (pin "2") (pinfunction "C_2") (pintype "passive"))
      (node (ref "OK1") (pin "4") (pinfunction "C_4") (pintype "passive"))
      (node (ref "OK2") (pin "5") (pinfunction "EMIT_5") (pintype "passive"))
      (node (ref "OK2") (pin "7") (pinfunction "EMIT_7") (pintype "passive"))
      (node (ref "R15") (pin "2") (pinfunction "2_2") (pintype "passive"))
      (node (ref "R2") (pin "1") (pinfunction "1_1") (pintype "passive"))
      (node (ref "R21") (pin "2") (pinfunction "2_2") (pintype "passive"))
      (node (ref "R22") (pin "2") (pinfunction "2_2") (pintype "passive"))
      (node (ref "R24") (pin "1") (pinfunction "1_1") (pintype "passive"))
      (node (ref "R3") (pin "2") (pinfunction "2_2") (pintype "passive"))
      (node (ref "R37") (pin "2") (pinfunction "2_2") (pintype "passive"))
      (node (ref "R5") (pin "1") (pinfunction "1_1") (pintype "passive"))
      (node (ref "R51") (pin "1") (pinfunction "1_1") (pintype "passive"))
      (node (ref "R52") (pin "1") (pinfunction "1_1") (pintype "passive"))
      (node (ref "R53") (pin "1") (pinfunction "1_1") (pintype "passive"))
      (node (ref "R55") (pin "1") (pinfunction "1_1") (pintype "passive"))
      (node (ref "R56") (pin "1") (pinfunction "1_1") (pintype "passive"))
      (node (ref "R57") (pin "1") (pinfunction "1_1") (pintype "passive"))
      (node (ref "R6") (pin "1") (pinfunction "1_1") (pintype "passive"))
      (node (ref "R9") (pin "1") (pinfunction "1_1") (pintype "passive"))
      (node (ref "SW1") (pin "1") (pinfunction "1_1") (pintype "passive"))
      (node (ref "SW1") (pin "2") (pinfunction "2_2") (pintype "passive"))
      (node (ref "SW1") (pin "5") (pinfunction "5-GND_5") (pintype "passive"))
      (node (ref "X1") (pin "1") (pinfunction "1_1") (pintype "power_in"))
      (node (ref "X2") (pin "3") (pinfunction "1_3") (pintype "passive"))
      (node (ref "X3") (pin "8") (pinfunction "1_8") (pintype "passive"))
      (node (ref "X4") (pin "2") (pinfunction "1_2") (pintype "passive"))
      (node (ref "X4") (pin "4") (pinfunction "1_4") (pintype "passive"))
      (node (ref "X5") (pin "12") (pinfunction "12_12") (pintype "passive"))
      (node (ref "X5") (pin "16") (pinfunction "16_16") (pintype "passive"))
      (node (ref "X5") (pin "20") (pinfunction "20_20") (pintype "passive"))
      (node (ref "X5") (pin "4") (pinfunction "4_4") (pintype "passive"))
      (node (ref "X5") (pin "8") (pinfunction "8_8") (pintype "passive"))
      (node (ref "X7") (pin "4") (pinfunction "SH_4") (pintype "input"))
      (node (ref "X7") (pin "5") (pinfunction "SH_5") (pintype "input"))
      (node (ref "X7") (pin "SH1") (pinfunction "SH_SH1") (pintype "input"))
      (node (ref "X7") (pin "SH2") (pinfunction "SH_SH2") (pintype "input"))
      (node (ref "X8") (pin "2") (pinfunction "1_2") (pintype "passive"))
      (node (ref "X8") (pin "4") (pinfunction "1_4") (pintype "passive"))
      (node (ref "X8") (pin "6") (pinfunction "1_6") (pintype "passive"))
      (node (ref "X9") (pin "19") (pinfunction "1_19") (pintype "passive"))
      (node (ref "X9") (pin "2") (pinfunction "1_2") (pintype "passive"))
      (node (ref "X9") (pin "20") (pinfunction "1_20") (pintype "passive"))
      (node (ref "X9") (pin "9") (pinfunction "1_9") (pintype "passive"))
      (node (ref "XO1") (pin "2") (pinfunction "GND_2") (pintype "power_in"))
      (node (ref "XO2") (pin "2") (pinfunction "GND_2") (pintype "power_in"))
      (node (ref "ZD3") (pin "A") (pinfunction "A_A") (pintype "passive"))
      (node (ref "ZD4") (pin "A") (pinfunction "A_A") (pintype "passive"))
      (node (ref "ZD5") (pin "A") (pinfunction "A_A") (pintype "passive"))
      (node (ref "ZD6") (pin "A") (pinfunction "A_A") (pintype "passive"))
    )
    (net (code "33") (name "GPIO38") (class "Default")
      (node (ref "IC18") (pin "5") (pinfunction "X0D38_5") (pintype "bidirectional"))
      (node (ref "X4") (pin "3") (pinfunction "1_3") (pintype "passive"))
    )
    (net (code "34") (name "GPIO39") (class "Default")
      (node (ref "IC18") (pin "7") (pinfunction "X0D39_7") (pintype "bidirectional"))
      (node (ref "X4") (pin "1") (pinfunction "1_1") (pintype "passive"))
    )
    (net (code "35") (name "IOEXP_DINP1") (class "Default")
      (node (ref "IC28") (pin "24") (pinfunction "GPA3_24") (pintype "bidirectional"))
      (node (ref "R58") (pin "2") (pinfunction "2_2") (pintype "passive"))
      (node (ref "ZD4") (pin "C") (pinfunction "C_C") (pintype "passive"))
    )
    (net (code "36") (name "IOEXP_DINP2") (class "Default")
      (node (ref "IC28") (pin "25") (pinfunction "GPA4_25") (pintype "bidirectional"))
      (node (ref "R59") (pin "2") (pinfunction "2_2") (pintype "passive"))
      (node (ref "ZD5") (pin "C") (pinfunction "C_C") (pintype "passive"))
    )
    (net (code "37") (name "IOEXP_DINP3") (class "Default")
      (node (ref "IC28") (pin "26") (pinfunction "GPA5_26") (pintype "bidirectional"))
      (node (ref "R60") (pin "2") (pinfunction "2_2") (pintype "passive"))
      (node (ref "ZD6") (pin "C") (pinfunction "C_C") (pintype "passive"))
    )
    (net (code "38") (name "IOEXP_LED1") (class "Default")
      (node (ref "IC28") (pin "21") (pinfunction "GPA0_21") (pintype "bidirectional"))
      (node (ref "LED1") (pin "A") (pinfunction "A_A") (pintype "passive"))
    )
    (net (code "39") (name "IOEXP_LED2") (class "Default")
      (node (ref "IC28") (pin "22") (pinfunction "GPA1_22") (pintype "bidirectional"))
      (node (ref "LED2") (pin "A") (pinfunction "A_A") (pintype "passive"))
    )
    (net (code "40") (name "IOEXP_OCI1") (class "Default")
      (node (ref "IC28") (pin "1") (pinfunction "GPB0_1") (pintype "bidirectional"))
      (node (ref "OK2") (pin "8") (pinfunction "COL_8") (pintype "passive"))
      (node (ref "R66") (pin "1") (pinfunction "1_1") (pintype "passive"))
    )
    (net (code "41") (name "IOEXP_OCI2") (class "Default")
      (node (ref "IC28") (pin "2") (pinfunction "GPB1_2") (pintype "bidirectional"))
      (node (ref "OK2") (pin "6") (pinfunction "COL_6") (pintype "passive"))
      (node (ref "R65") (pin "1") (pinfunction "1_1") (pintype "passive"))
    )
    (net (code "42") (name "IOEXP_OCO1") (class "Default")
      (node (ref "IC28") (pin "27") (pinfunction "GPA6_27") (pintype "bidirectional"))
      (node (ref "R61") (pin "2") (pinfunction "2_2") (pintype "passive"))
    )
    (net (code "43") (name "IOEXP_OCO2") (class "Default")
      (node (ref "IC28") (pin "28") (pinfunction "GPA7_28") (pintype "bidirectional"))
      (node (ref "R62") (pin "2") (pinfunction "2_2") (pintype "passive"))
    )
    (net (code "44") (name "IPEXP_LED3") (class "Default")
      (node (ref "IC28") (pin "23") (pinfunction "GPA2_23") (pintype "bidirectional"))
      (node (ref "LED3") (pin "A") (pinfunction "A_A") (pintype "passive"))
    )
    (net (code "45") (name "LATCH_IN") (class "Default")
      (node (ref "IC11") (pin "9") (pinfunction "3A_9") (pintype "passive"))
      (node (ref "X3") (pin "2") (pinfunction "1_2") (pintype "passive"))
    )
    (net (code "46") (name "LATCH_OUT") (class "Default")
      (node (ref "IC11") (pin "11") (pinfunction "3B1_11") (pintype "passive"))
      (node (ref "IC9") (pin "1") (pinfunction "CLK_1") (pintype "input"))
      (node (ref "R13") (pin "2") (pinfunction "2_2") (pintype "passive"))
    )
    (net (code "47") (name "LCD_0") (class "Default")
      (node (ref "IC3") (pin "15") (pinfunction "Q0/A_15") (pintype "output"))
      (node (ref "LCD1") (pin "8") (pinfunction "R3_8") (pintype "input"))
    )
    (net (code "48") (name "LCD_1") (class "Default")
      (node (ref "IC3") (pin "1") (pinfunction "Q1/B_1") (pintype "output"))
      (node (ref "LCD1") (pin "9") (pinfunction "R4_9") (pintype "input"))
    )
    (net (code "49") (name "LCD_2") (class "Default")
      (node (ref "IC3") (pin "2") (pinfunction "Q2/C_2") (pintype "output"))
      (node (ref "LCD1") (pin "10") (pinfunction "R5_10") (pintype "input"))
    )
    (net (code "50") (name "LCD_3") (class "Default")
      (node (ref "IC3") (pin "3") (pinfunction "Q3/D_3") (pintype "output"))
      (node (ref "LCD1") (pin "11") (pinfunction "R6_11") (pintype "input"))
    )
    (net (code "51") (name "LCD_4") (class "Default")
      (node (ref "IC3") (pin "4") (pinfunction "Q4/E_4") (pintype "output"))
      (node (ref "LCD1") (pin "12") (pinfunction "R7_12") (pintype "input"))
    )
    (net (code "52") (name "LCD_5") (class "Default")
      (node (ref "IC3") (pin "5") (pinfunction "Q5/F_5") (pintype "output"))
      (node (ref "LCD1") (pin "15") (pinfunction "G2_15") (pintype "input"))
    )
    (net (code "53") (name "LCD_6") (class "Default")
      (node (ref "IC3") (pin "6") (pinfunction "Q6/G_6") (pintype "output"))
      (node (ref "LCD1") (pin "16") (pinfunction "G3_16") (pintype "input"))
    )
    (net (code "54") (name "LCD_7") (class "Default")
      (node (ref "IC3") (pin "7") (pinfunction "Q7/H_7") (pintype "output"))
      (node (ref "LCD1") (pin "17") (pinfunction "G4_17") (pintype "input"))
    )
    (net (code "55") (name "LCD_8") (class "Default")
      (node (ref "IC5") (pin "15") (pinfunction "Q0/A_15") (pintype "output"))
      (node (ref "LCD1") (pin "18") (pinfunction "G5_18") (pintype "input"))
    )
    (net (code "56") (name "LCD_9") (class "Default")
      (node (ref "IC5") (pin "1") (pinfunction "Q1/B_1") (pintype "output"))
      (node (ref "LCD1") (pin "19") (pinfunction "G6_19") (pintype "input"))
    )
    (net (code "57") (name "LCD_10") (class "Default")
      (node (ref "IC5") (pin "2") (pinfunction "Q2/C_2") (pintype "output"))
      (node (ref "LCD1") (pin "20") (pinfunction "G7_20") (pintype "input"))
    )
    (net (code "58") (name "LCD_11") (class "Default")
      (node (ref "IC5") (pin "3") (pinfunction "Q3/D_3") (pintype "output"))
      (node (ref "LCD1") (pin "24") (pinfunction "B3_24") (pintype "input"))
    )
    (net (code "59") (name "LCD_12") (class "Default")
      (node (ref "IC5") (pin "4") (pinfunction "Q4/E_4") (pintype "output"))
      (node (ref "LCD1") (pin "25") (pinfunction "B4_25") (pintype "input"))
    )
    (net (code "60") (name "LCD_13") (class "Default")
      (node (ref "IC5") (pin "5") (pinfunction "Q5/F_5") (pintype "output"))
      (node (ref "LCD1") (pin "26") (pinfunction "B5_26") (pintype "input"))
    )
    (net (code "61") (name "LCD_14") (class "Default")
      (node (ref "IC5") (pin "6") (pinfunction "Q6/G_6") (pintype "output"))
      (node (ref "LCD1") (pin "27") (pinfunction "B6_27") (pintype "input"))
    )
    (net (code "62") (name "LCD_15") (class "Default")
      (node (ref "IC5") (pin "7") (pinfunction "Q7/H_7") (pintype "output"))
      (node (ref "LCD1") (pin "28") (pinfunction "B7_28") (pintype "input"))
    )
    (net (code "63") (name "LCD_CLK") (class "Default")
      (node (ref "IC18") (pin "88") (pinfunction "X0D24_88") (pintype "bidirectional"))
      (node (ref "LCD1") (pin "30") (pinfunction "CLK_30") (pintype "input"))
    )
    (net (code "64") (name "LCD_DE") (class "Default")
      (node (ref "IC18") (pin "66") (pinfunction "X0D23_66") (pintype "bidirectional"))
      (node (ref "LCD1") (pin "34") (pinfunction "DE/NC2_34") (pintype "passive"))
    )
    (net (code "65") (name "LCD_HSYNC") (class "Default")
      (node (ref "IC18") (pin "89") (pinfunction "X0D25_89") (pintype "bidirectional"))
      (node (ref "LCD1") (pin "32") (pinfunction "HSYNC_32") (pintype "input"))
    )
    (net (code "66") (name "LCD_VSYNC") (class "Default")
      (node (ref "IC18") (pin "64") (pinfunction "X0D22_64") (pintype "bidirectional"))
      (node (ref "LCD1") (pin "33") (pinfunction "VSYNC_33") (pintype "input"))
    )
    (net (code "67") (name "LED_ACT") (class "Default")
      (node (ref "IC24") (pin "26") (pinfunction "AN_EN(LED_ACT/COL)_26") (pintype "output"))
      (node (ref "R43") (pin "2") (pinfunction "2_2") (pintype "passive"))
      (node (ref "R49") (pin "2") (pinfunction "2_2") (pintype "passive"))
    )
    (net (code "68") (name "LED_LINK") (class "Default")
      (node (ref "IC24") (pin "28") (pinfunction "AN_0(LED_LINK)_28") (pintype "output"))
      (node (ref "R48") (pin "2") (pinfunction "2_2") (pintype "passive"))
      (node (ref "R50") (pin "2") (pinfunction "2_2") (pintype "passive"))
    )
    (net (code "69") (name "LED_SPEED") (class "Default")
      (node (ref "IC24") (pin "27") (pinfunction "AN_1(LED_SPEED)_27") (pintype "output"))
      (node (ref "R46") (pin "2") (pinfunction "2_2") (pintype "passive"))
      (node (ref "SPEED") (pin "C") (pinfunction "C_C") (pintype "passive"))
    )
    (net (code "70") (name "Net-(C59-Pad1)") (class "Default")
      (node (ref "C59") (pin "1") (pinfunction "1_1") (pintype "passive"))
      (node (ref "R35") (pin "2") (pinfunction "2_2") (pintype "passive"))
    )
    (net (code "71") (name "Net-(C61-Pad1)") (class "Default")
      (node (ref "C61") (pin "1") (pinfunction "1_1") (pintype "passive"))
      (node (ref "R33") (pin "1") (pinfunction "1_1") (pintype "passive"))
      (node (ref "R34") (pin "2") (pinfunction "2_2") (pintype "passive"))
    )
    (net (code "72") (name "Net-(C62-Pad1)") (class "Default")
      (node (ref "C62") (pin "1") (pinfunction "1_1") (pintype "passive"))
      (node (ref "R36") (pin "2") (pinfunction "2_2") (pintype "passive"))
    )
    (net (code "73") (name "Net-(C62-Pad2)") (class "Default")
      (node (ref "C62") (pin "2") (pinfunction "2_2") (pintype "passive"))
      (node (ref "R34") (pin "1") (pinfunction "1_1") (pintype "passive"))
    )
    (net (code "74") (name "Net-(C65-Pad1)") (class "Default")
      (node (ref "C65") (pin "1") (pinfunction "1_1") (pintype "passive"))
      (node (ref "R40") (pin "1") (pinfunction "1_1") (pintype "passive"))
      (node (ref "R41") (pin "2") (pinfunction "2_2") (pintype "passive"))
    )
    (net (code "75") (name "Net-(C67-Pad1)") (class "Default")
      (node (ref "C67") (pin "1") (pinfunction "1_1") (pintype "passive"))
      (node (ref "R44") (pin "1") (pinfunction "1_1") (pintype "passive"))
      (node (ref "R47") (pin "2") (pinfunction "2_2") (pintype "passive"))
    )
    (net (code "76") (name "Net-(C79-+)") (class "Default")
      (node (ref "C79") (pin "1") (pinfunction "+_1") (pintype "passive"))
      (node (ref "R54") (pin "1") (pinfunction "1_1") (pintype "passive"))
    )
    (net (code "77") (name "Net-(D3-PadA)") (class "Default")
      (node (ref "D3") (pin "A") (pinfunction "A_A") (pintype "passive"))
      (node (ref "R63") (pin "2") (pinfunction "2_2") (pintype "passive"))
    )
    (net (code "78") (name "Net-(D4-PadA)") (class "Default")
      (node (ref "D4") (pin "A") (pinfunction "A_A") (pintype "passive"))
      (node (ref "R64") (pin "2") (pinfunction "2_2") (pintype "passive"))
    )
    (net (code "79") (name "Net-(F1-P$1)") (class "Default")
      (node (ref "F1") (pin "1") (pinfunction "P$1_1") (pintype "bidirectional"))
      (node (ref "X1") (pin "2") (pinfunction "2_2") (pintype "power_in"))
    )
    (net (code "80") (name "Net-(F1-P$2)") (class "Default")
      (node (ref "F1") (pin "2") (pinfunction "P$2_2") (pintype "bidirectional"))
      (node (ref "Q1") (pin "3") (pinfunction "D_3") (pintype "passive"))
      (node (ref "ZD3") (pin "C") (pinfunction "C_C") (pintype "passive"))
    )
    (net (code "81") (name "Net-(FB1-2)") (class "Default")
      (node (ref "FB1") (pin "P$2") (pinfunction "2_P$2") (pintype "passive"))
      (node (ref "J1") (pin "1") (pinfunction "VCC_1") (pintype "passive"))
    )
    (net (code "82") (name "Net-(FB2-2)") (class "Default")
      (node (ref "FB2") (pin "P$2") (pinfunction "2_P$2") (pintype "passive"))
      (node (ref "J1") (pin "SH1") (pinfunction "SH1_SH1") (pintype "bidirectional"))
      (node (ref "J1") (pin "SH1.1") (pinfunction "SH1_SH1.1") (pintype "bidirectional"))
      (node (ref "J1") (pin "SH2") (pinfunction "SH2_SH2") (pintype "bidirectional"))
      (node (ref "J1") (pin "SH2.2") (pinfunction "SH2_SH2.2") (pintype "bidirectional"))
    )
    (net (code "83") (name "Net-(IC1-SW)") (class "Default")
      (node (ref "D1") (pin "A") (pinfunction "A_A") (pintype "passive"))
      (node (ref "IC1") (pin "1") (pinfunction "SW_1") (pintype "power_in"))
      (node (ref "L1") (pin "2") (pinfunction "2_2") (pintype "passive"))
    )
    (net (code "84") (name "Net-(IC1-VIN)") (class "Default")
      (node (ref "IC1") (pin "5") (pinfunction "VIN_5") (pintype "power_in"))
      (node (ref "R1") (pin "2") (pinfunction "2_2") (pintype "passive"))
    )
    (net (code "85") (name "Net-(IC2-SW)") (class "Default")
      (node (ref "C3") (pin "1") (pinfunction "1_1") (pintype "passive"))
      (node (ref "IC2") (pin "2") (pinfunction "SW_2") (pintype "output"))
      (node (ref "L2") (pin "1") (pinfunction "1_1") (pintype "passive"))
    )
    (net (code "86") (name "Net-(IC2-VBST)") (class "Default")
      (node (ref "C3") (pin "2") (pinfunction "2_2") (pintype "passive"))
      (node (ref "IC2") (pin "6") (pinfunction "VBST_6") (pintype "passive"))
    )
    (net (code "87") (name "Net-(IC2-VFB)") (class "Default")
      (node (ref "IC2") (pin "4") (pinfunction "VFB_4") (pintype "passive"))
      (node (ref "R4") (pin "1") (pinfunction "1_1") (pintype "passive"))
      (node (ref "R6") (pin "2") (pinfunction "2_2") (pintype "passive"))
    )
    (net (code "88") (name "Net-(IC3-~{Q7{slash}H})") (class "Default")
      (node (ref "IC3") (pin "9") (pinfunction "~{Q7/H}_9") (pintype "output"))
      (node (ref "IC5") (pin "14") (pinfunction "SER_14") (pintype "input"))
    )
    (net (code "89") (name "Net-(IC4-SW)") (class "Default")
      (node (ref "C7") (pin "1") (pinfunction "1_1") (pintype "passive"))
      (node (ref "IC4") (pin "2") (pinfunction "SW_2") (pintype "output"))
      (node (ref "L3") (pin "1") (pinfunction "1_1") (pintype "passive"))
    )
    (net (code "90") (name "Net-(IC4-VBST)") (class "Default")
      (node (ref "C7") (pin "2") (pinfunction "2_2") (pintype "passive"))
      (node (ref "IC4") (pin "6") (pinfunction "VBST_6") (pintype "passive"))
    )
    (net (code "91") (name "Net-(IC4-VFB)") (class "Default")
      (node (ref "IC4") (pin "4") (pinfunction "VFB_4") (pintype "passive"))
      (node (ref "R8") (pin "1") (pinfunction "1_1") (pintype "passive"))
      (node (ref "R9") (pin "2") (pinfunction "2_2") (pintype "passive"))
    )
    (net (code "92") (name "Net-(IC6-CT)") (class "Default")
      (node (ref "C14") (pin "1") (pinfunction "1_1") (pintype "passive"))
      (node (ref "IC6") (pin "4") (pinfunction "CT_4") (pintype "passive"))
    )
    (net (code "93") (name "Net-(IC7-WAKE)") (class "Default")
      (node (ref "IC7") (pin "5") (pinfunction "WAKE_5") (pintype "input"))
      (node (ref "R11") (pin "1") (pinfunction "1_1") (pintype "passive"))
    )
    (net (code "94") (name "Net-(IC7-X+)") (class "Default")
      (node (ref "IC7") (pin "18") (pinfunction "X+_18") (pintype "bidirectional"))
      (node (ref "LCD1") (pin "37") (pinfunction "XR_37") (pintype "passive"))
    )
    (net (code "95") (name "Net-(IC7-X-)") (class "Default")
      (node (ref "C16") (pin "1") (pinfunction "1_1") (pintype "passive"))
      (node (ref "IC7") (pin "19") (pinfunction "X-_19") (pintype "bidirectional"))
      (node (ref "LCD1") (pin "39") (pinfunction "XL_39") (pintype "passive"))
    )
    (net (code "96") (name "Net-(IC7-Y+)") (class "Default")
      (node (ref "IC7") (pin "15") (pinfunction "Y+_15") (pintype "bidirectional"))
      (node (ref "LCD1") (pin "40") (pinfunction "YU_40") (pintype "passive"))
    )
    (net (code "97") (name "Net-(IC7-Y-)") (class "Default")
      (node (ref "C15") (pin "1") (pinfunction "1_1") (pintype "passive"))
      (node (ref "IC7") (pin "16") (pinfunction "Y-_16") (pintype "bidirectional"))
      (node (ref "LCD1") (pin "38") (pinfunction "YD_38") (pintype "passive"))
      (node (ref "R11") (pin "2") (pinfunction "2_2") (pintype "passive"))
    )
    (net (code "98") (name "Net-(IC8-CT)") (class "Default")
      (node (ref "C20") (pin "1") (pinfunction "1_1") (pintype "passive"))
      (node (ref "IC8") (pin "4") (pinfunction "CT_4") (pintype "passive"))
    )
    (net (code "99") (name "Net-(IC8-~{MR})") (class "Default")
      (node (ref "C18") (pin "2") (pinfunction "2_2") (pintype "passive"))
      (node (ref "IC8") (pin "3") (pinfunction "~{MR}_3") (pintype "passive"))
      (node (ref "SW1") (pin "3") (pinfunction "3_3") (pintype "passive"))
      (node (ref "SW1") (pin "4") (pinfunction "4_4") (pintype "passive"))
    )
    (net (code "100") (name "Net-(IC9A-~{Q})") (class "Default")
      (node (ref "IC9") (pin "3") (pinfunction "~{Q}_3") (pintype "output"))
      (node (ref "X2") (pin "1") (pinfunction "1_1") (pintype "passive"))
    )
    (net (code "101") (name "Net-(IC10-CKE)") (class "Default")
      (node (ref "IC10") (pin "37") (pinfunction "CKE_37") (pintype "input"))
      (node (ref "R16") (pin "1") (pinfunction "1_1") (pintype "passive"))
    )
    (net (code "102") (name "Net-(IC10-LDQM)") (class "Default")
      (node (ref "IC10") (pin "15") (pinfunction "LDQM_15") (pintype "input"))
      (node (ref "IC10") (pin "39") (pinfunction "UDQM_39") (pintype "input"))
      (node (ref "IC12") (pin "4") (pinfunction "Y_4") (pintype "output"))
    )
    (net (code "103") (name "Net-(IC10-~{CS})") (class "Default")
      (node (ref "IC10") (pin "19") (pinfunction "~{CS}_19") (pintype "input"))
      (node (ref "R15") (pin "1") (pinfunction "1_1") (pintype "passive"))
    )
    (net (code "104") (name "Net-(IC17-SW)") (class "Default")
      (node (ref "C34") (pin "1") (pinfunction "1_1") (pintype "passive"))
      (node (ref "IC17") (pin "2") (pinfunction "SW_2") (pintype "output"))
      (node (ref "L4") (pin "1") (pinfunction "1_1") (pintype "passive"))
    )
    (net (code "105") (name "Net-(IC17-VBST)") (class "Default")
      (node (ref "C34") (pin "2") (pinfunction "2_2") (pintype "passive"))
      (node (ref "IC17") (pin "6") (pinfunction "VBST_6") (pintype "passive"))
    )
    (net (code "106") (name "Net-(IC17-VFB)") (class "Default")
      (node (ref "IC17") (pin "4") (pinfunction "VFB_4") (pintype "passive"))
      (node (ref "R23") (pin "1") (pinfunction "1_1") (pintype "passive"))
      (node (ref "R24") (pin "2") (pinfunction "2_2") (pintype "passive"))
    )
    (net (code "107") (name "Net-(IC18A-PLL_AVDD)") (class "Default")
      (node (ref "C57") (pin "1") (pinfunction "1_1") (pintype "passive"))
      (node (ref "IC18") (pin "103") (pinfunction "PLL_AVDD_103") (pintype "power_in"))
      (node (ref "R31") (pin "2") (pinfunction "2_2") (pintype "passive"))
    )
    (net (code "108") (name "Net-(IC18B-CLK)") (class "Default")
      (node (ref "IC18") (pin "125") (pinfunction "CLK_125") (pintype "passive"))
      (node (ref "R25") (pin "2") (pinfunction "2_2") (pintype "passive"))
    )
    (net (code "109") (name "Net-(IC18B-TCK)") (class "Default")
      (node (ref "IC18") (pin "128") (pinfunction "TCK_128") (pintype "passive"))
      (node (ref "R30") (pin "1") (pinfunction "1_1") (pintype "passive"))
    )
    (net (code "110") (name "Net-(IC18B-TMS)") (class "Default")
      (node (ref "IC18") (pin "127") (pinfunction "TMS_127") (pintype "passive"))
      (node (ref "R29") (pin "1") (pinfunction "1_1") (pintype "passive"))
    )
    (net (code "111") (name "Net-(IC18C-X0D42)") (class "Default")
      (node (ref "IC18") (pin "10") (pinfunction "X0D42_10") (pintype "bidirectional"))
      (node (ref "R27") (pin "1") (pinfunction "1_1") (pintype "passive"))
    )
    (net (code "112") (name "Net-(IC18C-X0D43)") (class "Default")
      (node (ref "IC18") (pin "12") (pinfunction "X0D43_12") (pintype "bidirectional"))
      (node (ref "R28") (pin "1") (pinfunction "1_1") (pintype "passive"))
    )
    (net (code "113") (name "Net-(IC18D-X1D26)") (class "Default")
      (node (ref "IC18") (pin "112") (pinfunction "X1D26_112") (pintype "bidirectional"))
      (node (ref "R42") (pin "1") (pinfunction "1_1") (pintype "passive"))
    )
    (net (code "114") (name "Net-(IC18E-USB_ID)") (class "Default")
      (node (ref "IC18") (pin "43") (pinfunction "USB_ID_43") (pintype "passive"))
      (node (ref "R67") (pin "1") (pinfunction "1_1") (pintype "passive"))
    )
    (net (code "115") (name "Net-(IC18E-USB_RTUNE)") (class "Default")
      (node (ref "IC18") (pin "48") (pinfunction "USB_RTUNE_48") (pintype "passive"))
      (node (ref "R22") (pin "1") (pinfunction "1_1") (pintype "passive"))
    )
    (net (code "116") (name "Net-(IC18E-USB_VBUS)") (class "Default")
      (node (ref "C31") (pin "1") (pinfunction "1_1") (pintype "passive"))
      (node (ref "IC18") (pin "45") (pinfunction "USB_VBUS_45") (pintype "passive"))
      (node (ref "R18") (pin "2") (pinfunction "2_2") (pintype "passive"))
    )
    (net (code "117") (name "Net-(IC22A-Y)") (class "Default")
      (node (ref "C60") (pin "1") (pinfunction "1_1") (pintype "passive"))
      (node (ref "IC22") (pin "4") (pinfunction "Y_4") (pintype "output"))
      (node (ref "R33") (pin "2") (pinfunction "2_2") (pintype "passive"))
    )
    (net (code "118") (name "Net-(IC23-BYPASS)") (class "Default")
      (node (ref "C64") (pin "2") (pinfunction "2_2") (pintype "passive"))
      (node (ref "IC23") (pin "2") (pinfunction "BYPASS_2") (pintype "input"))
    )
    (net (code "119") (name "Net-(IC23-IN+)") (class "Default")
      (node (ref "IC23") (pin "3") (pinfunction "IN+_3") (pintype "input"))
      (node (ref "R32") (pin "2") (pinfunction "2_2") (pintype "passive"))
      (node (ref "R35") (pin "1") (pinfunction "1_1") (pintype "passive"))
    )
    (net (code "120") (name "Net-(IC23-IN-)") (class "Default")
      (node (ref "IC23") (pin "4") (pinfunction "IN-_4") (pintype "input"))
      (node (ref "R36") (pin "1") (pinfunction "1_1") (pintype "passive"))
      (node (ref "R38") (pin "2") (pinfunction "2_2") (pintype "passive"))
    )
    (net (code "121") (name "Net-(IC23-VO+)") (class "Default")
      (node (ref "IC23") (pin "5") (pinfunction "VO+_5") (pintype "output"))
      (node (ref "R38") (pin "1") (pinfunction "1_1") (pintype "passive"))
      (node (ref "SP1") (pin "+") (pinfunction "+_+") (pintype "passive"))
      (node (ref "X6") (pin "2") (pinfunction "S_2") (pintype "passive"))
    )
    (net (code "122") (name "Net-(IC23-VO-)") (class "Default")
      (node (ref "IC23") (pin "8") (pinfunction "VO-_8") (pintype "output"))
      (node (ref "R32") (pin "1") (pinfunction "1_1") (pintype "passive"))
      (node (ref "SP1") (pin "-") (pinfunction "-_-") (pintype "passive"))
      (node (ref "X6") (pin "1") (pinfunction "S_1") (pintype "passive"))
    )
    (net (code "123") (name "Net-(IC24-PFBIN1)") (class "Default")
      (node (ref "C69") (pin "1") (pinfunction "1_1") (pintype "passive"))
      (node (ref "C70") (pin "1") (pinfunction "1_1") (pintype "passive"))
      (node (ref "C71") (pin "+") (pinfunction "+_+") (pintype "passive"))
      (node (ref "C72") (pin "1") (pinfunction "1_1") (pintype "passive"))
      (node (ref "IC24") (pin "18") (pinfunction "PFBIN1_18") (pintype "input"))
      (node (ref "IC24") (pin "23") (pinfunction "PFBOUT_23") (pintype "output"))
      (node (ref "IC24") (pin "37") (pinfunction "PFBIN2_37") (pintype "input"))
    )
    (net (code "124") (name "Net-(IC24-RBIAS)") (class "Default")
      (node (ref "IC24") (pin "24") (pinfunction "RBIAS_24") (pintype "input"))
      (node (ref "R53") (pin "2") (pinfunction "2_2") (pintype "passive"))
    )
    (net (code "125") (name "Net-(IC24-RD+)") (class "Default")
      (node (ref "IC24") (pin "14") (pinfunction "RD+_14") (pintype "bidirectional"))
      (node (ref "R44") (pin "2") (pinfunction "2_2") (pintype "passive"))
      (node (ref "X7") (pin "7") (pinfunction "RD+_7") (pintype "input"))
    )
    (net (code "126") (name "Net-(IC24-RD-)") (class "Default")
      (node (ref "IC24") (pin "13") (pinfunction "RD-_13") (pintype "bidirectional"))
      (node (ref "R47") (pin "1") (pinfunction "1_1") (pintype "passive"))
      (node (ref "X7") (pin "8") (pinfunction "RD-_8") (pintype "input"))
    )
    (net (code "127") (name "Net-(IC24-RESERVED-20)") (class "Default")
      (node (ref "IC24") (pin "20") (pinfunction "RESERVED-20_20") (pintype "bidirectional"))
      (node (ref "R52") (pin "2") (pinfunction "2_2") (pintype "passive"))
    )
    (net (code "128") (name "Net-(IC24-RESERVED-21)") (class "Default")
      (node (ref "IC24") (pin "21") (pinfunction "RESERVED-21_21") (pintype "bidirectional"))
      (node (ref "R51") (pin "2") (pinfunction "2_2") (pintype "passive"))
    )
    (net (code "129") (name "Net-(IC24-TD+)") (class "Default")
      (node (ref "IC24") (pin "17") (pinfunction "TD+_17") (pintype "bidirectional"))
      (node (ref "R40") (pin "2") (pinfunction "2_2") (pintype "passive"))
      (node (ref "X7") (pin "1") (pinfunction "TD+_1") (pintype "input"))
    )
    (net (code "130") (name "Net-(IC24-TD-)") (class "Default")
      (node (ref "IC24") (pin "16") (pinfunction "TD-_16") (pintype "bidirectional"))
      (node (ref "R41") (pin "1") (pinfunction "1_1") (pintype "passive"))
      (node (ref "X7") (pin "2") (pinfunction "TD-_2") (pintype "input"))
    )
    (net (code "131") (name "Net-(IC24-X1)") (class "Default")
      (node (ref "IC24") (pin "34") (pinfunction "X1_34") (pintype "input"))
      (node (ref "R39") (pin "2") (pinfunction "2_2") (pintype "passive"))
    )
    (net (code "132") (name "Net-(IC27-OSCI)") (class "Default")
      (node (ref "IC27") (pin "1") (pinfunction "OSCI_1") (pintype "input"))
      (node (ref "Y1") (pin "1") (pinfunction "1_1") (pintype "passive"))
    )
    (net (code "133") (name "Net-(IC27-OSCO)") (class "Default")
      (node (ref "IC27") (pin "2") (pinfunction "OSCO_2") (pintype "output"))
      (node (ref "Y1") (pin "4") (pinfunction "2_4") (pintype "passive"))
    )
    (net (code "134") (name "Net-(IC27-VDD)") (class "Default")
      (node (ref "C78") (pin "2") (pinfunction "2_2") (pintype "passive"))
      (node (ref "D2") (pin "C") (pinfunction "C_C") (pintype "passive"))
      (node (ref "IC27") (pin "14") (pinfunction "VDD_14") (pintype "power_in"))
      (node (ref "R54") (pin "2") (pinfunction "2_2") (pintype "passive"))
    )
    (net (code "135") (name "Net-(LCD1-DISP)") (class "Default")
      (node (ref "LCD1") (pin "31") (pinfunction "DISP_31") (pintype "input"))
      (node (ref "R7") (pin "1") (pinfunction "1_1") (pintype "passive"))
    )
    (net (code "136") (name "Net-(LED1-PadC)") (class "Default")
      (node (ref "LED1") (pin "C") (pinfunction "C_C") (pintype "passive"))
      (node (ref "R55") (pin "2") (pinfunction "2_2") (pintype "passive"))
    )
    (net (code "137") (name "Net-(LED2-PadC)") (class "Default")
      (node (ref "LED2") (pin "C") (pinfunction "C_C") (pintype "passive"))
      (node (ref "R56") (pin "2") (pinfunction "2_2") (pintype "passive"))
    )
    (net (code "138") (name "Net-(LED3-PadC)") (class "Default")
      (node (ref "LED3") (pin "C") (pinfunction "C_C") (pintype "passive"))
      (node (ref "R57") (pin "2") (pinfunction "2_2") (pintype "passive"))
    )
    (net (code "139") (name "Net-(OK1A-A)") (class "Default")
      (node (ref "OK1") (pin "1") (pinfunction "A_1") (pintype "passive"))
      (node (ref "R61") (pin "1") (pinfunction "1_1") (pintype "passive"))
    )
    (net (code "140") (name "Net-(OK1A-COL)") (class "Default")
      (node (ref "OK1") (pin "8") (pinfunction "COL_8") (pintype "passive"))
      (node (ref "X8") (pin "10") (pinfunction "1_10") (pintype "passive"))
      (node (ref "ZD7") (pin "C") (pinfunction "C_C") (pintype "passive"))
    )
    (net (code "141") (name "Net-(OK1A-EMIT)") (class "Default")
      (node (ref "OK1") (pin "7") (pinfunction "EMIT_7") (pintype "passive"))
      (node (ref "X8") (pin "9") (pinfunction "1_9") (pintype "passive"))
      (node (ref "ZD7") (pin "A") (pinfunction "A_A") (pintype "passive"))
    )
    (net (code "142") (name "Net-(OK1B-A)") (class "Default")
      (node (ref "OK1") (pin "3") (pinfunction "A_3") (pintype "passive"))
      (node (ref "R62") (pin "1") (pinfunction "1_1") (pintype "passive"))
    )
    (net (code "143") (name "Net-(OK1B-COL)") (class "Default")
      (node (ref "OK1") (pin "6") (pinfunction "COL_6") (pintype "passive"))
      (node (ref "X8") (pin "8") (pinfunction "1_8") (pintype "passive"))
      (node (ref "ZD8") (pin "C") (pinfunction "C_C") (pintype "passive"))
    )
    (net (code "144") (name "Net-(OK1B-EMIT)") (class "Default")
      (node (ref "OK1") (pin "5") (pinfunction "EMIT_5") (pintype "passive"))
      (node (ref "X8") (pin "7") (pinfunction "1_7") (pintype "passive"))
      (node (ref "ZD8") (pin "A") (pinfunction "A_A") (pintype "passive"))
    )
    (net (code "145") (name "Net-(OK2A-A)") (class "Default")
      (node (ref "D3") (pin "C") (pinfunction "C_C") (pintype "passive"))
      (node (ref "OK2") (pin "1") (pinfunction "A_1") (pintype "passive"))
    )
    (net (code "146") (name "Net-(OK2A-C)") (class "Default")
      (node (ref "OK2") (pin "2") (pinfunction "C_2") (pintype "passive"))
      (node (ref "X8") (pin "11") (pinfunction "1_11") (pintype "passive"))
    )
    (net (code "147") (name "Net-(OK2B-A)") (class "Default")
      (node (ref "D4") (pin "C") (pinfunction "C_C") (pintype "passive"))
      (node (ref "OK2") (pin "3") (pinfunction "A_3") (pintype "passive"))
    )
    (net (code "148") (name "Net-(OK2B-C)") (class "Default")
      (node (ref "OK2") (pin "4") (pinfunction "C_4") (pintype "passive"))
      (node (ref "X8") (pin "13") (pinfunction "1_13") (pintype "passive"))
    )
    (net (code "149") (name "Net-(PWR_3V3-PadC)") (class "Default")
      (node (ref "PWR_3V3") (pin "C") (pinfunction "C_C") (pintype "passive"))
      (node (ref "R5") (pin "2") (pinfunction "2_2") (pintype "passive"))
    )
    (net (code "150") (name "Net-(Q1-G)") (class "Default")
      (node (ref "Q1") (pin "1") (pinfunction "G_1") (pintype "passive"))
      (node (ref "R2") (pin "2") (pinfunction "2_2") (pintype "passive"))
      (node (ref "ZD2") (pin "A") (pinfunction "A_A") (pintype "passive"))
    )
    (net (code "151") (name "Net-(R45-Pad2)") (class "Default")
      (node (ref "R45") (pin "2") (pinfunction "2_2") (pintype "passive"))
      (node (ref "SPEED") (pin "A") (pinfunction "A_A") (pintype "passive"))
    )
    (net (code "152") (name "Net-(R58-Pad1)") (class "Default")
      (node (ref "R58") (pin "1") (pinfunction "1_1") (pintype "passive"))
      (node (ref "X8") (pin "1") (pinfunction "1_1") (pintype "passive"))
    )
    (net (code "153") (name "Net-(X3D-1)") (class "Default")
      (node (ref "R17") (pin "1") (pinfunction "1_1") (pintype "passive"))
      (node (ref "X3") (pin "4") (pinfunction "1_4") (pintype "passive"))
    )
    (net (code "154") (name "Net-(X7-GREEN-C)") (class "Default")
      (node (ref "R50") (pin "1") (pinfunction "1_1") (pintype "passive"))
      (node (ref "X7") (pin "10") (pinfunction "GREEN-C_10") (pintype "passive"))
    )
    (net (code "155") (name "Net-(X7-YELLOW-C)") (class "Default")
      (node (ref "R49") (pin "1") (pinfunction "1_1") (pintype "passive"))
      (node (ref "X7") (pin "11") (pinfunction "YELLOW-C_11") (pintype "passive"))
    )
    (net (code "156") (name "Net-(X8D-1)") (class "Default")
      (node (ref "R63") (pin "1") (pinfunction "1_1") (pintype "passive"))
      (node (ref "X8") (pin "12") (pinfunction "1_12") (pintype "passive"))
    )
    (net (code "157") (name "Net-(X8F-1)") (class "Default")
      (node (ref "R64") (pin "1") (pinfunction "1_1") (pintype "passive"))
      (node (ref "X8") (pin "14") (pinfunction "1_14") (pintype "passive"))
    )
    (net (code "158") (name "Net-(X8H-1)") (class "Default")
      (node (ref "R59") (pin "1") (pinfunction "1_1") (pintype "passive"))
      (node (ref "X8") (pin "3") (pinfunction "1_3") (pintype "passive"))
    )
    (net (code "159") (name "Net-(X8J-1)") (class "Default")
      (node (ref "R60") (pin "1") (pinfunction "1_1") (pintype "passive"))
      (node (ref "X8") (pin "5") (pinfunction "1_5") (pintype "passive"))
    )
    (net (code "160") (name "Net-(XO1-OUT)") (class "Default")
      (node (ref "R25") (pin "1") (pinfunction "1_1") (pintype "passive"))
      (node (ref "XO1") (pin "3") (pinfunction "OUT_3") (pintype "output"))
    )
    (net (code "161") (name "Net-(XO2-OUT)") (class "Default")
      (node (ref "R39") (pin "1") (pinfunction "1_1") (pintype "passive"))
      (node (ref "XO2") (pin "3") (pinfunction "OUT_3") (pintype "output"))
    )
    (net (code "162") (name "QSPI_CLK") (class "Default")
      (node (ref "IC11") (pin "5") (pinfunction "2B1_5") (pintype "passive"))
      (node (ref "IC13") (pin "6") (pinfunction "SCK_6") (pintype "input"))
      (node (ref "X2") (pin "9") (pinfunction "1_9") (pintype "passive"))
    )
    (net (code "163") (name "QSPI_D0") (class "Default")
      (node (ref "IC13") (pin "5") (pinfunction "SI/IO0_5") (pintype "bidirectional"))
      (node (ref "IC14") (pin "2") (pinfunction "1B1_2") (pintype "passive"))
      (node (ref "X2") (pin "8") (pinfunction "1_8") (pintype "passive"))
    )
    (net (code "164") (name "QSPI_D1") (class "Default")
      (node (ref "IC13") (pin "2") (pinfunction "SO/IO1_2") (pintype "bidirectional"))
      (node (ref "IC14") (pin "5") (pinfunction "2B1_5") (pintype "passive"))
      (node (ref "X2") (pin "7") (pinfunction "1_7") (pintype "passive"))
    )
    (net (code "165") (name "QSPI_D2") (class "Default")
      (node (ref "IC13") (pin "3") (pinfunction "~{WP}/IO2_3") (pintype "bidirectional"))
      (node (ref "IC14") (pin "11") (pinfunction "3B1_11") (pintype "passive"))
      (node (ref "X2") (pin "6") (pinfunction "1_6") (pintype "passive"))
    )
    (net (code "166") (name "QSPI_D3") (class "Default")
      (node (ref "IC13") (pin "7") (pinfunction "~{HOLD}/IO3_7") (pintype "bidirectional"))
      (node (ref "IC14") (pin "14") (pinfunction "4B1_14") (pintype "passive"))
      (node (ref "X2") (pin "5") (pinfunction "1_5") (pintype "passive"))
    )
    (net (code "167") (name "SD_ADQ0") (class "Default")
      (node (ref "IC10") (pin "2") (pinfunction "DQ0_2") (pintype "bidirectional"))
      (node (ref "IC10") (pin "23") (pinfunction "A0_23") (pintype "input"))
      (node (ref "IC18") (pin "37") (pinfunction "X0D02_37") (pintype "bidirectional"))
    )
    (net (code "168") (name "SD_ADQ1") (class "Default")
      (node (ref "IC10") (pin "24") (pinfunction "A1_24") (pintype "input"))
      (node (ref "IC10") (pin "4") (pinfunction "DQ1_4") (pintype "bidirectional"))
      (node (ref "IC18") (pin "38") (pinfunction "X0D03_38") (pintype "bidirectional"))
    )
    (net (code "169") (name "SD_ADQ2") (class "Default")
      (node (ref "IC10") (pin "25") (pinfunction "A2_25") (pintype "input"))
      (node (ref "IC10") (pin "5") (pinfunction "DQ2_5") (pintype "bidirectional"))
      (node (ref "IC14") (pin "3") (pinfunction "1B2_3") (pintype "passive"))
    )
    (net (code "170") (name "SD_ADQ3") (class "Default")
      (node (ref "IC10") (pin "26") (pinfunction "A3_26") (pintype "input"))
      (node (ref "IC10") (pin "7") (pinfunction "DQ3_7") (pintype "bidirectional"))
      (node (ref "IC14") (pin "6") (pinfunction "2B2_6") (pintype "passive"))
    )
    (net (code "171") (name "SD_ADQ4") (class "Default")
      (node (ref "IC10") (pin "29") (pinfunction "A4_29") (pintype "input"))
      (node (ref "IC10") (pin "8") (pinfunction "DQ4_8") (pintype "bidirectional"))
      (node (ref "IC14") (pin "10") (pinfunction "3B2_10") (pintype "passive"))
    )
    (net (code "172") (name "SD_ADQ5") (class "Default")
      (node (ref "IC10") (pin "10") (pinfunction "DQ5_10") (pintype "bidirectional"))
      (node (ref "IC10") (pin "30") (pinfunction "A5_30") (pintype "input"))
      (node (ref "IC14") (pin "13") (pinfunction "4B2_13") (pintype "passive"))
    )
    (net (code "173") (name "SD_ADQ6") (class "Default")
      (node (ref "IC10") (pin "11") (pinfunction "DQ6_11") (pintype "bidirectional"))
      (node (ref "IC10") (pin "31") (pinfunction "A6_31") (pintype "input"))
      (node (ref "IC18") (pin "39") (pinfunction "X0D08_39") (pintype "bidirectional"))
    )
    (net (code "174") (name "SD_ADQ7") (class "Default")
      (node (ref "IC10") (pin "13") (pinfunction "DQ7_13") (pintype "bidirectional"))
      (node (ref "IC10") (pin "32") (pinfunction "A7_32") (pintype "input"))
      (node (ref "IC18") (pin "40") (pinfunction "X0D09_40") (pintype "bidirectional"))
    )
    (net (code "175") (name "SD_ADQ8") (class "Default")
      (node (ref "IC10") (pin "33") (pinfunction "A8_33") (pintype "input"))
      (node (ref "IC10") (pin "42") (pinfunction "DQ8_42") (pintype "bidirectional"))
      (node (ref "IC18") (pin "57") (pinfunction "X0D14_57") (pintype "bidirectional"))
    )
    (net (code "176") (name "SD_ADQ9") (class "Default")
      (node (ref "IC10") (pin "34") (pinfunction "A9_34") (pintype "input"))
      (node (ref "IC10") (pin "44") (pinfunction "DQ9_44") (pintype "bidirectional"))
      (node (ref "IC18") (pin "58") (pinfunction "X0D15_58") (pintype "bidirectional"))
    )
    (net (code "177") (name "SD_ADQ10") (class "Default")
      (node (ref "IC10") (pin "22") (pinfunction "A10/AP_22") (pintype "input"))
      (node (ref "IC10") (pin "45") (pinfunction "DQ10_45") (pintype "bidirectional"))
      (node (ref "IC18") (pin "68") (pinfunction "X0D16_68") (pintype "bidirectional"))
    )
    (net (code "178") (name "SD_ADQ11") (class "Default")
      (node (ref "IC10") (pin "35") (pinfunction "A11_35") (pintype "input"))
      (node (ref "IC10") (pin "47") (pinfunction "DQ11_47") (pintype "bidirectional"))
      (node (ref "IC18") (pin "69") (pinfunction "X0D17_69") (pintype "bidirectional"))
    )
    (net (code "179") (name "SD_ADQ12") (class "Default")
      (node (ref "IC10") (pin "36") (pinfunction "A12/NC-36_36") (pintype "passive"))
      (node (ref "IC10") (pin "48") (pinfunction "DQ12_48") (pintype "bidirectional"))
      (node (ref "IC18") (pin "70") (pinfunction "X0D18_70") (pintype "bidirectional"))
    )
    (net (code "180") (name "SD_ADQ13") (class "Default")
      (node (ref "IC10") (pin "20") (pinfunction "BA0_20") (pintype "input"))
      (node (ref "IC10") (pin "50") (pinfunction "DQ13_50") (pintype "bidirectional"))
      (node (ref "IC18") (pin "71") (pinfunction "X0D19_71") (pintype "bidirectional"))
    )
    (net (code "181") (name "SD_ADQ14") (class "Default")
      (node (ref "IC10") (pin "21") (pinfunction "BA1_21") (pintype "input"))
      (node (ref "IC10") (pin "51") (pinfunction "DQ14_51") (pintype "bidirectional"))
      (node (ref "IC18") (pin "59") (pinfunction "X0D20_59") (pintype "bidirectional"))
    )
    (net (code "182") (name "SD_ADQ15") (class "Default")
      (node (ref "IC10") (pin "53") (pinfunction "DQ15_53") (pintype "bidirectional"))
      (node (ref "IC18") (pin "61") (pinfunction "X0D21_61") (pintype "bidirectional"))
    )
    (net (code "183") (name "SD_CLK") (class "Default")
      (node (ref "IC10") (pin "38") (pinfunction "CLK_38") (pintype "input"))
      (node (ref "IC18") (pin "63") (pinfunction "X0D13_63") (pintype "bidirectional"))
    )
    (net (code "184") (name "SPI0_CLK") (class "Default")
      (node (ref "IC18") (pin "100") (pinfunction "X0D31_100") (pintype "bidirectional"))
      (node (ref "IC3") (pin "11") (pinfunction "SRCLK_11") (pintype "input"))
      (node (ref "IC5") (pin "11") (pinfunction "SRCLK_11") (pintype "input"))
    )
    (net (code "185") (name "SPI0_MOSI") (class "Default")
      (node (ref "IC18") (pin "93") (pinfunction "X0D26_93") (pintype "bidirectional"))
      (node (ref "IC3") (pin "14") (pinfunction "SER_14") (pintype "input"))
    )
    (net (code "186") (name "SPI0_STROBE") (class "Default")
      (node (ref "IC18") (pin "95") (pinfunction "X0D32_95") (pintype "bidirectional"))
      (node (ref "IC3") (pin "12") (pinfunction "RCLK_12") (pintype "input"))
      (node (ref "IC5") (pin "12") (pinfunction "RCLK_12") (pintype "input"))
    )
    (net (code "187") (name "SPI1_CLK") (class "Default")
      (node (ref "IC18") (pin "94") (pinfunction "X0D27_94") (pintype "bidirectional"))
      (node (ref "IC26") (pin "11") (pinfunction "SRCLK_11") (pintype "input"))
      (node (ref "IC27") (pin "10") (pinfunction "SCL_10") (pintype "bidirectional"))
      (node (ref "IC28") (pin "12") (pinfunction "SCK_12") (pintype "input"))
      (node (ref "IC29") (pin "6") (pinfunction "SCK_6") (pintype "input"))
      (node (ref "IC7") (pin "11") (pinfunction "SCK/SCL/TX_11") (pintype "bidirectional"))
      (node (ref "J2") (pin "4") (pinfunction "VDD_4") (pintype "power_in"))
      (node (ref "MOD1") (pin "5") (pinfunction "SCLK_5") (pintype "input"))
    )
    (net (code "188") (name "SPI1_MISO") (class "Default")
      (node (ref "IC18") (pin "91") (pinfunction "X0D35_91") (pintype "bidirectional"))
      (node (ref "IC27") (pin "8") (pinfunction "SDO_8") (pintype "passive"))
      (node (ref "IC28") (pin "14") (pinfunction "SO_14") (pintype "passive"))
      (node (ref "IC29") (pin "2") (pinfunction "SO_2") (pintype "output"))
      (node (ref "IC7") (pin "9") (pinfunction "SDO_9") (pintype "bidirectional"))
      (node (ref "J2") (pin "6") (pinfunction "VSS_6") (pintype "power_in"))
      (node (ref "MOD1") (pin "2") (pinfunction "MISO_2") (pintype "passive"))
    )
    (net (code "189") (name "SPI1_MOSI") (class "Default")
      (node (ref "IC18") (pin "99") (pinfunction "X0D30_99") (pintype "bidirectional"))
      (node (ref "IC26") (pin "14") (pinfunction "SER_14") (pintype "input"))
      (node (ref "IC27") (pin "9") (pinfunction "SDI_9") (pintype "input"))
      (node (ref "IC28") (pin "13") (pinfunction "SI_13") (pintype "input"))
      (node (ref "IC29") (pin "5") (pinfunction "SI_5") (pintype "input"))
      (node (ref "IC7") (pin "13") (pinfunction "SDI/SDA/RX_13") (pintype "bidirectional"))
      (node (ref "J2") (pin "2") (pinfunction "CD/DAT3_2") (pintype "passive"))
      (node (ref "MOD1") (pin "3") (pinfunction "MOSI_3") (pintype "passive"))
    )
    (net (code "190") (name "SPI1_SELECT") (class "Default")
      (node (ref "IC18") (pin "97") (pinfunction "X0D33_97") (pintype "bidirectional"))
      (node (ref "IC26") (pin "12") (pinfunction "RCLK_12") (pintype "input"))
    )
    (net (code "191") (name "SPI2_CLK") (class "Default")
      (node (ref "IC18") (pin "96") (pinfunction "X0D28_96") (pintype "bidirectional"))
      (node (ref "X9") (pin "3") (pinfunction "1_3") (pintype "passive"))
    )
    (net (code "192") (name "SPI2_MISO") (class "Default")
      (node (ref "IC18") (pin "3") (pinfunction "X0D36_3") (pintype "bidirectional"))
      (node (ref "X9") (pin "4") (pinfunction "1_4") (pintype "passive"))
    )
    (net (code "193") (name "SPI2_MOSI") (class "Default")
      (node (ref "IC18") (pin "98") (pinfunction "X0D29_98") (pintype "bidirectional"))
      (node (ref "X9") (pin "5") (pinfunction "1_5") (pintype "passive"))
    )
    (net (code "194") (name "SPI2_SELECT") (class "Default")
      (node (ref "IC18") (pin "90") (pinfunction "X0D34_90") (pintype "bidirectional"))
      (node (ref "X9") (pin "6") (pinfunction "1_6") (pintype "passive"))
    )
    (net (code "195") (name "SPI_INT") (class "Default")
      (node (ref "IC18") (pin "13") (pinfunction "X1D35_13") (pintype "bidirectional"))
      (node (ref "IC28") (pin "19") (pinfunction "INTB_19") (pintype "passive"))
      (node (ref "IC28") (pin "20") (pinfunction "INTA_20") (pintype "passive"))
    )
    (net (code "196") (name "TCK") (class "Default")
      (node (ref "IC19") (pin "5") (pinfunction "IO4_5") (pintype "bidirectional"))
      (node (ref "R30") (pin "2") (pinfunction "2_2") (pintype "passive"))
      (node (ref "X5") (pin "9") (pinfunction "9_9") (pintype "passive"))
    )
    (net (code "197") (name "TDI") (class "Default")
      (node (ref "IC18") (pin "2") (pinfunction "TDI_2") (pintype "passive"))
      (node (ref "IC19") (pin "1") (pinfunction "IO1_1") (pintype "bidirectional"))
      (node (ref "X5") (pin "5") (pinfunction "5_5") (pintype "passive"))
    )
    (net (code "198") (name "TDO") (class "Default")
      (node (ref "IC18") (pin "1") (pinfunction "TDO_1") (pintype "passive"))
      (node (ref "IC19") (pin "4") (pinfunction "IO3_4") (pintype "bidirectional"))
      (node (ref "X5") (pin "13") (pinfunction "13_13") (pintype "passive"))
    )
    (net (code "199") (name "TMS") (class "Default")
      (node (ref "IC19") (pin "2") (pinfunction "IO2_2") (pintype "bidirectional"))
      (node (ref "R29") (pin "2") (pinfunction "2_2") (pintype "passive"))
      (node (ref "X5") (pin "7") (pinfunction "7_7") (pintype "passive"))
    )
    (net (code "200") (name "TRST_N") (class "Default")
      (node (ref "IC21") (pin "2") (pinfunction "A_2") (pintype "input"))
      (node (ref "R26") (pin "2") (pinfunction "2_2") (pintype "passive"))
      (node (ref "X5") (pin "15") (pinfunction "15_15") (pintype "passive"))
    )
    (net (code "201") (name "USB_D_N") (class "Default")
      (node (ref "IC16") (pin "2") (pinfunction "IO1_2") (pintype "bidirectional"))
      (node (ref "IC18") (pin "47") (pinfunction "USB_DM_47") (pintype "passive"))
      (node (ref "J1") (pin "2") (pinfunction "D-_2") (pintype "passive"))
    )
    (net (code "202") (name "USB_D_P") (class "Default")
      (node (ref "IC16") (pin "3") (pinfunction "IO2_3") (pintype "bidirectional"))
      (node (ref "IC18") (pin "46") (pinfunction "USB_DP_46") (pintype "passive"))
      (node (ref "J1") (pin "3") (pinfunction "D+_3") (pintype "passive"))
    )
    (net (code "203") (name "USB_ID") (class "Default")
      (node (ref "IC28") (pin "8") (pinfunction "GPB7_8") (pintype "bidirectional"))
      (node (ref "J1") (pin "4") (pinfunction "ID_4") (pintype "passive"))
      (node (ref "R20") (pin "2") (pinfunction "2_2") (pintype "passive"))
    )
    (net (code "204") (name "USB_VBUS") (class "Default")
      (node (ref "C32") (pin "1") (pinfunction "1_1") (pintype "passive"))
      (node (ref "C33") (pin "2") (pinfunction "2_2") (pintype "passive"))
      (node (ref "FB1") (pin "P$1") (pinfunction "1_P$1") (pintype "passive"))
      (node (ref "IC15") (pin "1") (pinfunction "OUT_1") (pintype "output"))
      (node (ref "IC16") (pin "4") (pinfunction "VCC_4") (pintype "power_in"))
      (node (ref "R18") (pin "1") (pinfunction "1_1") (pintype "passive"))
      (node (ref "R21") (pin "1") (pinfunction "1_1") (pintype "passive"))
    )
    (net (code "205") (name "VBUS_EN") (class "Default")
      (node (ref "IC15") (pin "4") (pinfunction "EN_4") (pintype "input"))
      (node (ref "IC17") (pin "5") (pinfunction "EN_5") (pintype "input"))
      (node (ref "IC26") (pin "7") (pinfunction "Q7/H_7") (pintype "output"))
    )
    (net (code "206") (name "VIN") (class "Default")
      (node (ref "C4") (pin "1") (pinfunction "1_1") (pintype "passive"))
      (node (ref "C40") (pin "1") (pinfunction "1_1") (pintype "passive"))
      (node (ref "C8") (pin "1") (pinfunction "1_1") (pintype "passive"))
      (node (ref "IC17") (pin "3") (pinfunction "VIN_3") (pintype "input"))
      (node (ref "IC2") (pin "3") (pinfunction "VIN_3") (pintype "input"))
      (node (ref "IC2") (pin "5") (pinfunction "EN_5") (pintype "input"))
      (node (ref "IC4") (pin "3") (pinfunction "VIN_3") (pintype "input"))
      (node (ref "Q1") (pin "2") (pinfunction "S_2") (pintype "passive"))
      (node (ref "ZD2") (pin "C") (pinfunction "C_C") (pintype "passive"))
    )
    (net (code "207") (name "VLED+") (class "Default")
      (node (ref "C1") (pin "1") (pinfunction "1_1") (pintype "passive"))
      (node (ref "D1") (pin "C") (pinfunction "C_C") (pintype "passive"))
      (node (ref "LCD1") (pin "2") (pinfunction "VLED+_2") (pintype "power_in"))
      (node (ref "ZD1") (pin "C") (pinfunction "C_C") (pintype "passive"))
    )
    (net (code "208") (name "VLED-") (class "Default")
      (node (ref "IC1") (pin "3") (pinfunction "FB_3") (pintype "input"))
      (node (ref "LCD1") (pin "1") (pinfunction "VLED-_1") (pintype "power_in"))
      (node (ref "R3") (pin "1") (pinfunction "1_1") (pintype "passive"))
      (node (ref "ZD1") (pin "A") (pinfunction "A_A") (pintype "passive"))
    )
    (net (code "209") (name "X0D00{slash}LATCH") (class "Default")
      (node (ref "IC18") (pin "30") (pinfunction "X0D00_30") (pintype "bidirectional"))
      (node (ref "X3") (pin "1") (pinfunction "1_1") (pintype "passive"))
    )
    (net (code "210") (name "X0D01{slash}~{QS_CS}") (class "Default")
      (node (ref "IC11") (pin "4") (pinfunction "1A_4") (pintype "passive"))
      (node (ref "IC18") (pin "27") (pinfunction "X0D01_27") (pintype "bidirectional"))
    )
    (net (code "211") (name "X0D04{slash}QS_D0") (class "Default")
      (node (ref "IC14") (pin "4") (pinfunction "1A_4") (pintype "passive"))
      (node (ref "IC18") (pin "31") (pinfunction "X0D04_31") (pintype "bidirectional"))
    )
    (net (code "212") (name "X0D05{slash}QS_D1") (class "Default")
      (node (ref "IC14") (pin "7") (pinfunction "2A_7") (pintype "passive"))
      (node (ref "IC18") (pin "33") (pinfunction "X0D05_33") (pintype "bidirectional"))
      (node (ref "X3") (pin "5") (pinfunction "1_5") (pintype "passive"))
    )
    (net (code "213") (name "X0D06{slash}QS_D2") (class "Default")
      (node (ref "IC14") (pin "9") (pinfunction "3A_9") (pintype "passive"))
      (node (ref "IC18") (pin "34") (pinfunction "X0D06_34") (pintype "bidirectional"))
    )
    (net (code "214") (name "X0D07{slash}QS_D3") (class "Default")
      (node (ref "IC14") (pin "12") (pinfunction "4A_12") (pintype "passive"))
      (node (ref "IC18") (pin "35") (pinfunction "X0D07_35") (pintype "bidirectional"))
    )
    (net (code "215") (name "X0D10{slash}QS_CLK") (class "Default")
      (node (ref "IC11") (pin "7") (pinfunction "2A_7") (pintype "passive"))
      (node (ref "IC18") (pin "28") (pinfunction "X0D10_28") (pintype "bidirectional"))
      (node (ref "X3") (pin "6") (pinfunction "1_6") (pintype "passive"))
    )
    (net (code "216") (name "X0D11{slash}LCD_BR") (class "Default")
      (node (ref "IC1") (pin "4") (pinfunction "CTRL_4") (pintype "input"))
      (node (ref "IC18") (pin "32") (pinfunction "X0D11_32") (pintype "bidirectional"))
      (node (ref "X3") (pin "3") (pinfunction "1_3") (pintype "passive"))
    )
    (net (code "217") (name "XL_DN0") (class "Default")
      (node (ref "IC18") (pin "9") (pinfunction "X0D41_9") (pintype "bidirectional"))
      (node (ref "IC20") (pin "1") (pinfunction "IO1_1") (pintype "bidirectional"))
      (node (ref "X5") (pin "14") (pinfunction "14_14") (pintype "passive"))
    )
    (net (code "218") (name "XL_DN1") (class "Default")
      (node (ref "IC18") (pin "8") (pinfunction "X0D40_8") (pintype "bidirectional"))
      (node (ref "IC20") (pin "2") (pinfunction "IO2_2") (pintype "bidirectional"))
      (node (ref "X5") (pin "18") (pinfunction "18_18") (pintype "passive"))
    )
    (net (code "219") (name "XL_UP0") (class "Default")
      (node (ref "IC20") (pin "5") (pinfunction "IO4_5") (pintype "bidirectional"))
      (node (ref "R27") (pin "2") (pinfunction "2_2") (pintype "passive"))
      (node (ref "X5") (pin "10") (pinfunction "10_10") (pintype "passive"))
    )
    (net (code "220") (name "XL_UP1") (class "Default")
      (node (ref "IC20") (pin "4") (pinfunction "IO3_4") (pintype "bidirectional"))
      (node (ref "R28") (pin "2") (pinfunction "2_2") (pintype "passive"))
      (node (ref "X5") (pin "6") (pinfunction "6_6") (pintype "passive"))
    )
    (net (code "221") (name "unconnected-(IC5-~{Q7{slash}H}-Pad9)") (class "Default")
      (node (ref "IC5") (pin "9") (pinfunction "~{Q7/H}_9") (pintype "output"))
    )
    (net (code "222") (name "unconnected-(IC6-~{MR}-Pad3)") (class "Default")
      (node (ref "IC6") (pin "3") (pinfunction "~{MR}_3") (pintype "passive"))
    )
    (net (code "223") (name "unconnected-(IC7-M2-Pad4)") (class "Default")
      (node (ref "IC7") (pin "4") (pinfunction "M2_4") (pintype "input"))
    )
    (net (code "224") (name "unconnected-(IC7-SIQ-Pad6)") (class "Default")
      (node (ref "IC7") (pin "6") (pinfunction "SIQ_6") (pintype "bidirectional"))
    )
    (net (code "225") (name "unconnected-(IC9A-Q-Pad5)") (class "Default")
      (node (ref "IC9") (pin "5") (pinfunction "Q_5") (pintype "output"))
    )
    (net (code "226") (name "unconnected-(IC10-NC-40-Pad40)") (class "Default")
      (node (ref "IC10") (pin "40") (pinfunction "NC-40_40") (pintype "no_connect"))
    )
    (net (code "227") (name "unconnected-(IC11-4B1-Pad14)") (class "Default")
      (node (ref "IC11") (pin "14") (pinfunction "4B1_14") (pintype "passive"))
    )
    (net (code "228") (name "unconnected-(IC11-4B2-Pad13)") (class "Default")
      (node (ref "IC11") (pin "13") (pinfunction "4B2_13") (pintype "passive"))
    )
    (net (code "229") (name "unconnected-(IC18A-NC-50-Pad50)") (class "Default")
      (node (ref "IC18") (pin "50") (pinfunction "NC-50_50") (pintype "no_connect"))
    )
    (net (code "230") (name "unconnected-(IC18A-NC-65-Pad65)") (class "Default")
      (node (ref "IC18") (pin "65") (pinfunction "NC-65_65") (pintype "no_connect"))
    )
    (net (code "231") (name "unconnected-(IC18D-X1D00-Pad85)") (class "Default")
      (node (ref "IC18") (pin "85") (pinfunction "X1D00_85") (pintype "bidirectional"))
    )
    (net (code "232") (name "unconnected-(IC18D-X1D01-Pad86)") (class "Default")
      (node (ref "IC18") (pin "86") (pinfunction "X1D01_86") (pintype "bidirectional"))
    )
    (net (code "233") (name "unconnected-(IC18D-X1D02-Pad72)") (class "Default")
      (node (ref "IC18") (pin "72") (pinfunction "X1D02_72") (pintype "bidirectional"))
    )
    (net (code "234") (name "unconnected-(IC18D-X1D03-Pad74)") (class "Default")
      (node (ref "IC18") (pin "74") (pinfunction "X1D03_74") (pintype "bidirectional"))
    )
    (net (code "235") (name "unconnected-(IC18D-X1D04-Pad75)") (class "Default")
      (node (ref "IC18") (pin "75") (pinfunction "X1D04_75") (pintype "bidirectional"))
    )
    (net (code "236") (name "unconnected-(IC18D-X1D05-Pad76)") (class "Default")
      (node (ref "IC18") (pin "76") (pinfunction "X1D05_76") (pintype "bidirectional"))
    )
    (net (code "237") (name "unconnected-(IC18D-X1D06-Pad77)") (class "Default")
      (node (ref "IC18") (pin "77") (pinfunction "X1D06_77") (pintype "bidirectional"))
    )
    (net (code "238") (name "unconnected-(IC18D-X1D07-Pad79)") (class "Default")
      (node (ref "IC18") (pin "79") (pinfunction "X1D07_79") (pintype "bidirectional"))
    )
    (net (code "239") (name "unconnected-(IC18D-X1D08-Pad82)") (class "Default")
      (node (ref "IC18") (pin "82") (pinfunction "X1D08_82") (pintype "bidirectional"))
    )
    (net (code "240") (name "unconnected-(IC18D-X1D09-Pad84)") (class "Default")
      (node (ref "IC18") (pin "84") (pinfunction "X1D09_84") (pintype "bidirectional"))
    )
    (net (code "241") (name "unconnected-(IC18D-X1D14-Pad51)") (class "Default")
      (node (ref "IC18") (pin "51") (pinfunction "X1D14_51") (pintype "bidirectional"))
    )
    (net (code "242") (name "unconnected-(IC18D-X1D15-Pad53)") (class "Default")
      (node (ref "IC18") (pin "53") (pinfunction "X1D15_53") (pintype "bidirectional"))
    )
    (net (code "243") (name "unconnected-(IC18D-X1D16-Pad22)") (class "Default")
      (node (ref "IC18") (pin "22") (pinfunction "X1D16_22") (pintype "bidirectional"))
    )
    (net (code "244") (name "unconnected-(IC18D-X1D17-Pad23)") (class "Default")
      (node (ref "IC18") (pin "23") (pinfunction "X1D17_23") (pintype "bidirectional"))
    )
    (net (code "245") (name "unconnected-(IC18D-X1D18-Pad25)") (class "Default")
      (node (ref "IC18") (pin "25") (pinfunction "X1D18_25") (pintype "bidirectional"))
    )
    (net (code "246") (name "unconnected-(IC18D-X1D19-Pad26)") (class "Default")
      (node (ref "IC18") (pin "26") (pinfunction "X1D19_26") (pintype "bidirectional"))
    )
    (net (code "247") (name "unconnected-(IC18D-X1D20-Pad54)") (class "Default")
      (node (ref "IC18") (pin "54") (pinfunction "X1D20_54") (pintype "bidirectional"))
    )
    (net (code "248") (name "unconnected-(IC18D-X1D21-Pad55)") (class "Default")
      (node (ref "IC18") (pin "55") (pinfunction "X1D21_55") (pintype "bidirectional"))
    )
    (net (code "249") (name "unconnected-(IC18D-X1D38-Pad20)") (class "Default")
      (node (ref "IC18") (pin "20") (pinfunction "X1D38_20") (pintype "bidirectional"))
    )
    (net (code "250") (name "unconnected-(IC18D-X1D39-Pad21)") (class "Default")
      (node (ref "IC18") (pin "21") (pinfunction "X1D39_21") (pintype "bidirectional"))
    )
    (net (code "251") (name "unconnected-(IC24-CLK_OUT-Pad25)") (class "Default")
      (node (ref "IC24") (pin "25") (pinfunction "CLK_OUT_25") (pintype "output"))
    )
    (net (code "252") (name "unconnected-(IC24-CRS{slash}CRS_DV{slash}LED_CFG-Pad40)") (class "Default")
      (node (ref "IC24") (pin "40") (pinfunction "CRS/CRS_DV/LED_CFG_40") (pintype "output"))
    )
    (net (code "253") (name "unconnected-(IC24-PHYAD0(COL)-Pad42)") (class "Default")
      (node (ref "IC24") (pin "42") (pinfunction "PHYAD0(COL)_42") (pintype "output"))
    )
    (net (code "254") (name "unconnected-(IC24-PWR_DOWN{slash}INT-Pad7)") (class "Default")
      (node (ref "IC24") (pin "7") (pinfunction "PWR_DOWN/INT_7") (pintype "input"))
    )
    (net (code "255") (name "unconnected-(IC24-TCK-Pad8)") (class "Default")
      (node (ref "IC24") (pin "8") (pinfunction "TCK_8") (pintype "input"))
    )
    (net (code "256") (name "unconnected-(IC24-TDI-Pad12)") (class "Default")
      (node (ref "IC24") (pin "12") (pinfunction "TDI_12") (pintype "input"))
    )
    (net (code "257") (name "unconnected-(IC24-TDO-Pad9)") (class "Default")
      (node (ref "IC24") (pin "9") (pinfunction "TDO_9") (pintype "output"))
    )
    (net (code "258") (name "unconnected-(IC24-TMS-Pad10)") (class "Default")
      (node (ref "IC24") (pin "10") (pinfunction "TMS_10") (pintype "input"))
    )
    (net (code "259") (name "unconnected-(IC24-X2-Pad33)") (class "Default")
      (node (ref "IC24") (pin "33") (pinfunction "X2_33") (pintype "output"))
    )
    (net (code "260") (name "unconnected-(IC24-~{TRST}-Pad11)") (class "Default")
      (node (ref "IC24") (pin "11") (pinfunction "~{TRST}_11") (pintype "input"))
    )
    (net (code "261") (name "unconnected-(IC26-~{Q7{slash}H}-Pad9)") (class "Default")
      (node (ref "IC26") (pin "9") (pinfunction "~{Q7/H}_9") (pintype "output"))
    )
    (net (code "262") (name "unconnected-(IC27-CLKOUT-Pad13)") (class "Default")
      (node (ref "IC27") (pin "13") (pinfunction "CLKOUT_13") (pintype "output"))
    )
    (net (code "263") (name "unconnected-(J2-DAT0-Pad7)") (class "Default")
      (node (ref "J2") (pin "7") (pinfunction "DAT0_7") (pintype "passive"))
    )
    (net (code "264") (name "unconnected-(J2-DAT1-Pad8)") (class "Default")
      (node (ref "J2") (pin "8") (pinfunction "DAT1_8") (pintype "passive"))
    )
    (net (code "265") (name "unconnected-(LCD1-NC1-Pad35)") (class "Default")
      (node (ref "LCD1") (pin "35") (pinfunction "NC1_35") (pintype "no_connect"))
    )
    (net (code "266") (name "unconnected-(R67-Pad2)") (class "Default")
      (node (ref "R67") (pin "2") (pinfunction "2_2") (pintype "passive"))
    )
    (net (code "267") (name "unconnected-(X5-Pad1)") (class "Default")
      (node (ref "X5") (pin "1") (pinfunction "1_1") (pintype "passive"))
    )
    (net (code "268") (name "unconnected-(X5-Pad2)") (class "Default")
      (node (ref "X5") (pin "2") (pinfunction "2_2") (pintype "passive"))
    )
    (net (code "269") (name "unconnected-(X5-Pad3)") (class "Default")
      (node (ref "X5") (pin "3") (pinfunction "3_3") (pintype "passive"))
    )
    (net (code "270") (name "unconnected-(X5-Pad11)") (class "Default")
      (node (ref "X5") (pin "11") (pinfunction "11_11") (pintype "passive"))
    )
    (net (code "271") (name "unconnected-(X5-Pad17)") (class "Default")
      (node (ref "X5") (pin "17") (pinfunction "17_17") (pintype "passive"))
    )
    (net (code "272") (name "unconnected-(X5-Pad19)") (class "Default")
      (node (ref "X5") (pin "19") (pinfunction "19_19") (pintype "passive"))
    )
    (net (code "273") (name "unconnected-(XO1-EN-Pad1)") (class "Default")
      (node (ref "XO1") (pin "1") (pinfunction "EN_1") (pintype "input"))
    )
    (net (code "274") (name "unconnected-(XO2-EN-Pad1)") (class "Default")
      (node (ref "XO2") (pin "1") (pinfunction "EN_1") (pintype "input"))
    )
    (net (code "275") (name "~{AUDIO_SHDN}") (class "Default")
      (node (ref "IC23") (pin "1") (pinfunction "~{SHDN}_1") (pintype "input"))
      (node (ref "IC26") (pin "6") (pinfunction "Q6/G_6") (pintype "output"))
      (node (ref "R37") (pin "1") (pinfunction "1_1") (pintype "passive"))
    )
    (net (code "276") (name "~{QSPI_CS}") (class "Default")
      (node (ref "IC11") (pin "2") (pinfunction "1B1_2") (pintype "passive"))
      (node (ref "IC13") (pin "1") (pinfunction "~{CS}_1") (pintype "input"))
      (node (ref "R14") (pin "2") (pinfunction "2_2") (pintype "passive"))
      (node (ref "X2") (pin "10") (pinfunction "1_10") (pintype "passive"))
    )
    (net (code "277") (name "~{QSPI_SEL}") (class "Default")
      (node (ref "IC11") (pin "1") (pinfunction "S_1") (pintype "input"))
      (node (ref "IC14") (pin "1") (pinfunction "S_1") (pintype "input"))
      (node (ref "X2") (pin "2") (pinfunction "1_2") (pintype "passive"))
      (node (ref "X2") (pin "4") (pinfunction "1_4") (pintype "passive"))
    )
    (net (code "278") (name "~{RESET}") (class "Default")
      (node (ref "IC18") (pin "123") (pinfunction "TRST_N_123") (pintype "passive"))
      (node (ref "IC18") (pin "124") (pinfunction "RST_N_124") (pintype "passive"))
      (node (ref "IC21") (pin "4") (pinfunction "Y_4") (pintype "output"))
      (node (ref "IC28") (pin "18") (pinfunction "~{RESET}_18") (pintype "input"))
      (node (ref "IC8") (pin "1") (pinfunction "~{RESET}_1") (pintype "output"))
      (node (ref "IC9") (pin "6") (pinfunction "~{CLR}_6") (pintype "input"))
      (node (ref "LCD1") (pin "36") (pinfunction "RESET_36") (pintype "input"))
      (node (ref "R12") (pin "2") (pinfunction "2_2") (pintype "passive"))
    )
    (net (code "279") (name "~{RIVERDI_INT}") (class "Default")
      (node (ref "IC28") (pin "5") (pinfunction "GPB4_5") (pintype "bidirectional"))
      (node (ref "X9") (pin "7") (pinfunction "1_7") (pintype "passive"))
    )
    (net (code "280") (name "~{RIVERDI_PD}") (class "Default")
      (node (ref "IC26") (pin "5") (pinfunction "Q5/F_5") (pintype "output"))
      (node (ref "X9") (pin "8") (pinfunction "1_8") (pintype "passive"))
    )
    (net (code "281") (name "~{RTC_INT}") (class "Default")
      (node (ref "IC27") (pin "5") (pinfunction "~{INT}_5") (pintype "output"))
      (node (ref "IC28") (pin "3") (pinfunction "GPB2_3") (pintype "bidirectional"))
    )
    (net (code "282") (name "~{SD_CAS}") (class "Default")
      (node (ref "IC10") (pin "17") (pinfunction "~{CAS}_17") (pintype "input"))
      (node (ref "IC11") (pin "3") (pinfunction "1B2_3") (pintype "passive"))
      (node (ref "IC12") (pin "1") (pinfunction "A_1") (pintype "input"))
    )
    (net (code "283") (name "~{SD_DETECT}") (class "Default")
      (node (ref "IC28") (pin "6") (pinfunction "GPB5_6") (pintype "bidirectional"))
      (node (ref "J2") (pin "SW1") (pinfunction "SW1_SW1") (pintype "passive"))
    )
    (net (code "284") (name "~{SD_RAS}") (class "Default")
      (node (ref "IC10") (pin "18") (pinfunction "~{RAS}_18") (pintype "input"))
      (node (ref "IC11") (pin "10") (pinfunction "3B2_10") (pintype "passive"))
    )
    (net (code "285") (name "~{SD_WE}") (class "Default")
      (node (ref "IC10") (pin "16") (pinfunction "~{WE}_16") (pintype "input"))
      (node (ref "IC11") (pin "6") (pinfunction "2B2_6") (pintype "passive"))
      (node (ref "IC12") (pin "2") (pinfunction "B_2") (pintype "input"))
    )
    (net (code "286") (name "~{SPI0_TOUCH}") (class "Default")
      (node (ref "IC18") (pin "4") (pinfunction "X0D37_4") (pintype "bidirectional"))
      (node (ref "IC7") (pin "8") (pinfunction "SS_8") (pintype "bidirectional"))
    )
    (net (code "287") (name "~{SPI1_EEPROM}") (class "Default")
      (node (ref "IC26") (pin "4") (pinfunction "Q4/E_4") (pintype "output"))
      (node (ref "IC29") (pin "1") (pinfunction "~{CS}_1") (pintype "input"))
    )
    (net (code "288") (name "~{SPI1_IOEXP}") (class "Default")
      (node (ref "IC26") (pin "1") (pinfunction "Q1/B_1") (pintype "output"))
      (node (ref "IC28") (pin "11") (pinfunction "~{CS}_11") (pintype "input"))
    )
    (net (code "289") (name "~{SPI1_RTC}") (class "Default")
      (node (ref "IC26") (pin "15") (pinfunction "Q0/A_15") (pintype "output"))
      (node (ref "IC27") (pin "6") (pinfunction "CE_6") (pintype "input"))
    )
    (net (code "290") (name "~{SPI1_SDCARD}") (class "Default")
      (node (ref "IC26") (pin "3") (pinfunction "Q3/D_3") (pintype "output"))
      (node (ref "J2") (pin "1") (pinfunction "DAT2_1") (pintype "passive"))
    )
    (net (code "291") (name "~{SPI1_W5500}") (class "Default")
      (node (ref "IC26") (pin "2") (pinfunction "Q2/C_2") (pintype "output"))
      (node (ref "MOD1") (pin "4") (pinfunction "SCS_4") (pintype "input"))
    )
    (net (code "292") (name "~{USB_OC}") (class "Default")
      (node (ref "IC15") (pin "3") (pinfunction "~{OC}_3") (pintype "passive"))
      (node (ref "IC28") (pin "7") (pinfunction "GPB6_7") (pintype "bidirectional"))
      (node (ref "R19") (pin "1") (pinfunction "1_1") (pintype "passive"))
    )
    (net (code "293") (name "~{W5500_INT}") (class "Default")
      (node (ref "IC28") (pin "4") (pinfunction "GPB3_4") (pintype "bidirectional"))
      (node (ref "MOD1") (pin "9") (pinfunction "INT_9") (pintype "passive"))
    )
  )
)
